# XMICRO-MEMORY.net
KiCad netlist of a schematic drawn in EAGLE
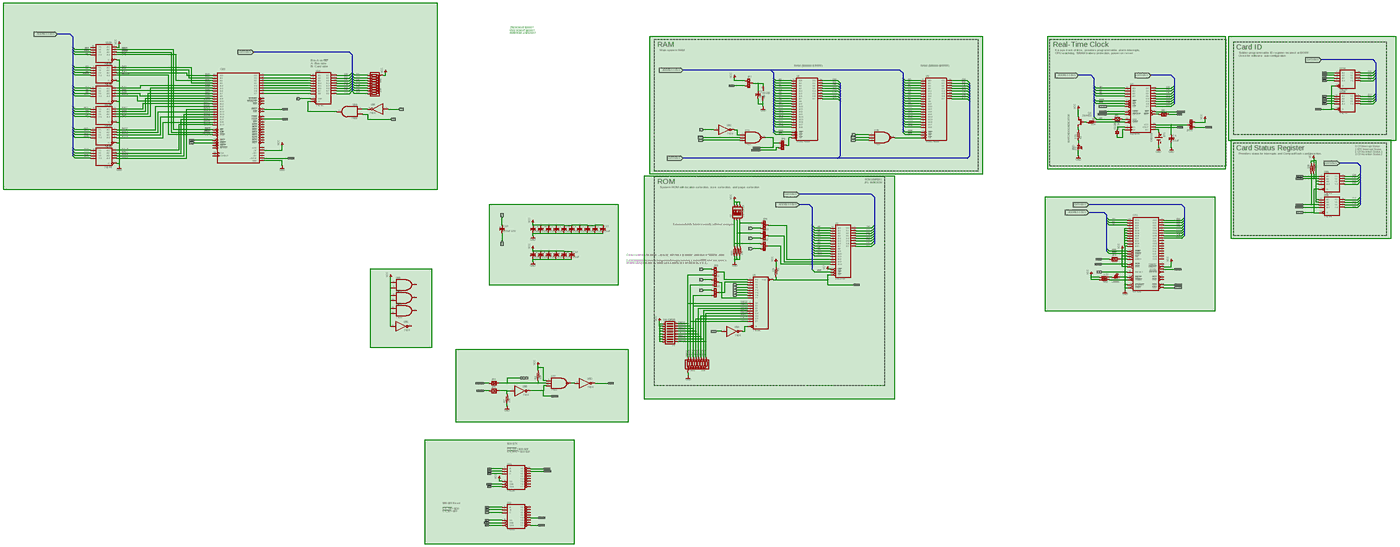
[diagram p0: schematic, sheet 1, overview]
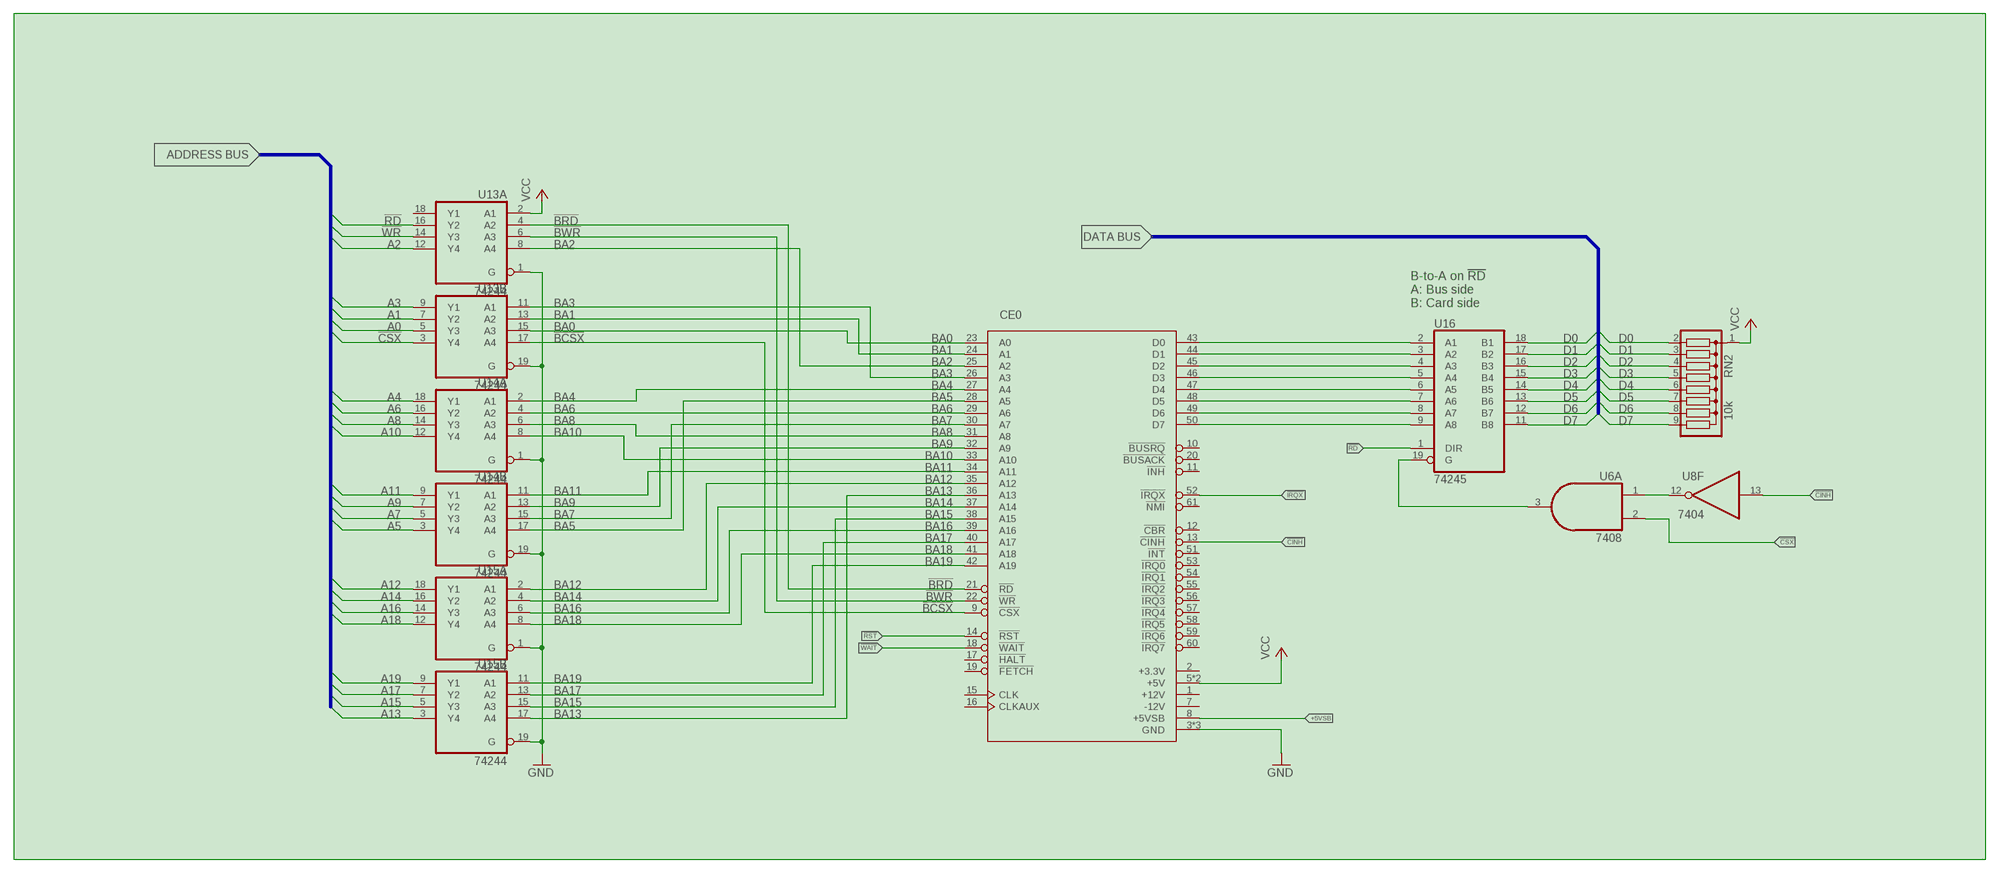
[diagram p1: schematic, sheet 1, part 1 of 6]
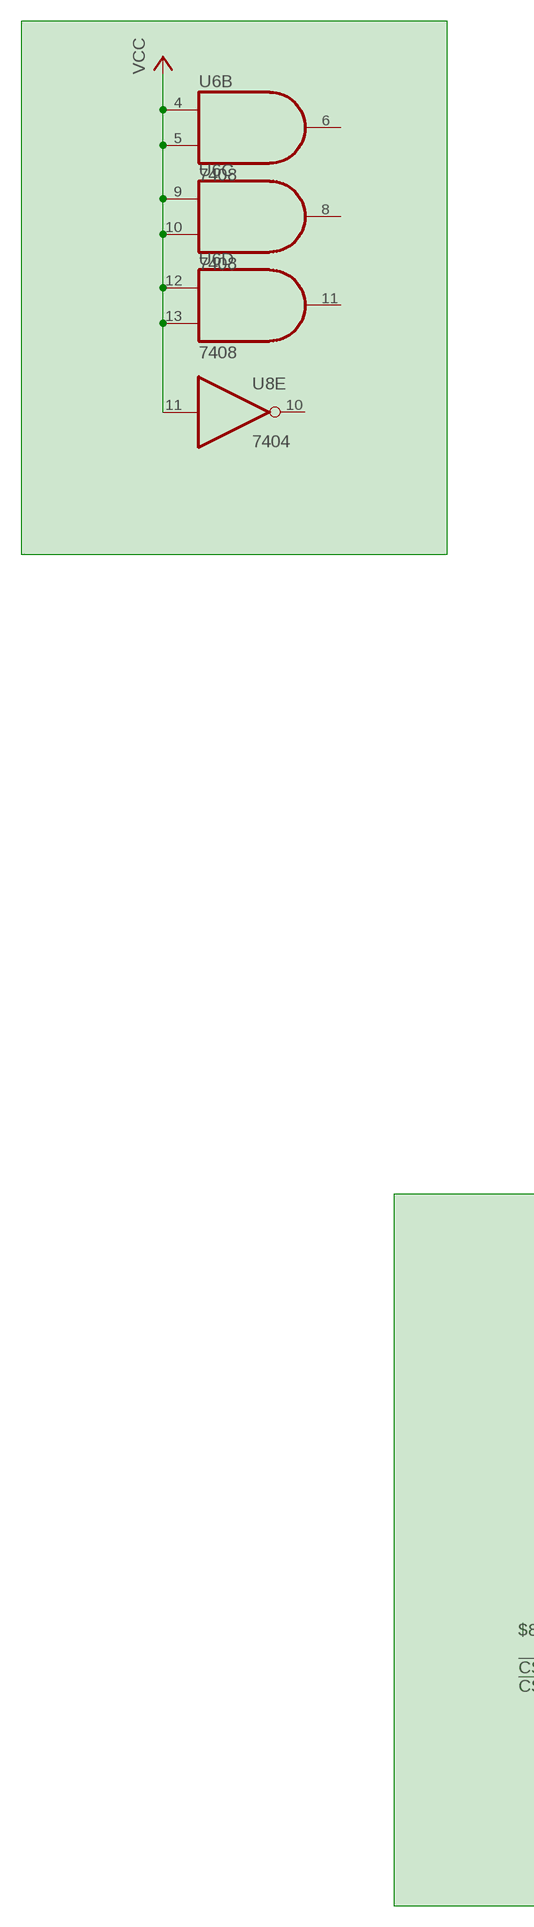
[diagram p2: schematic, sheet 1, part 2 of 6]
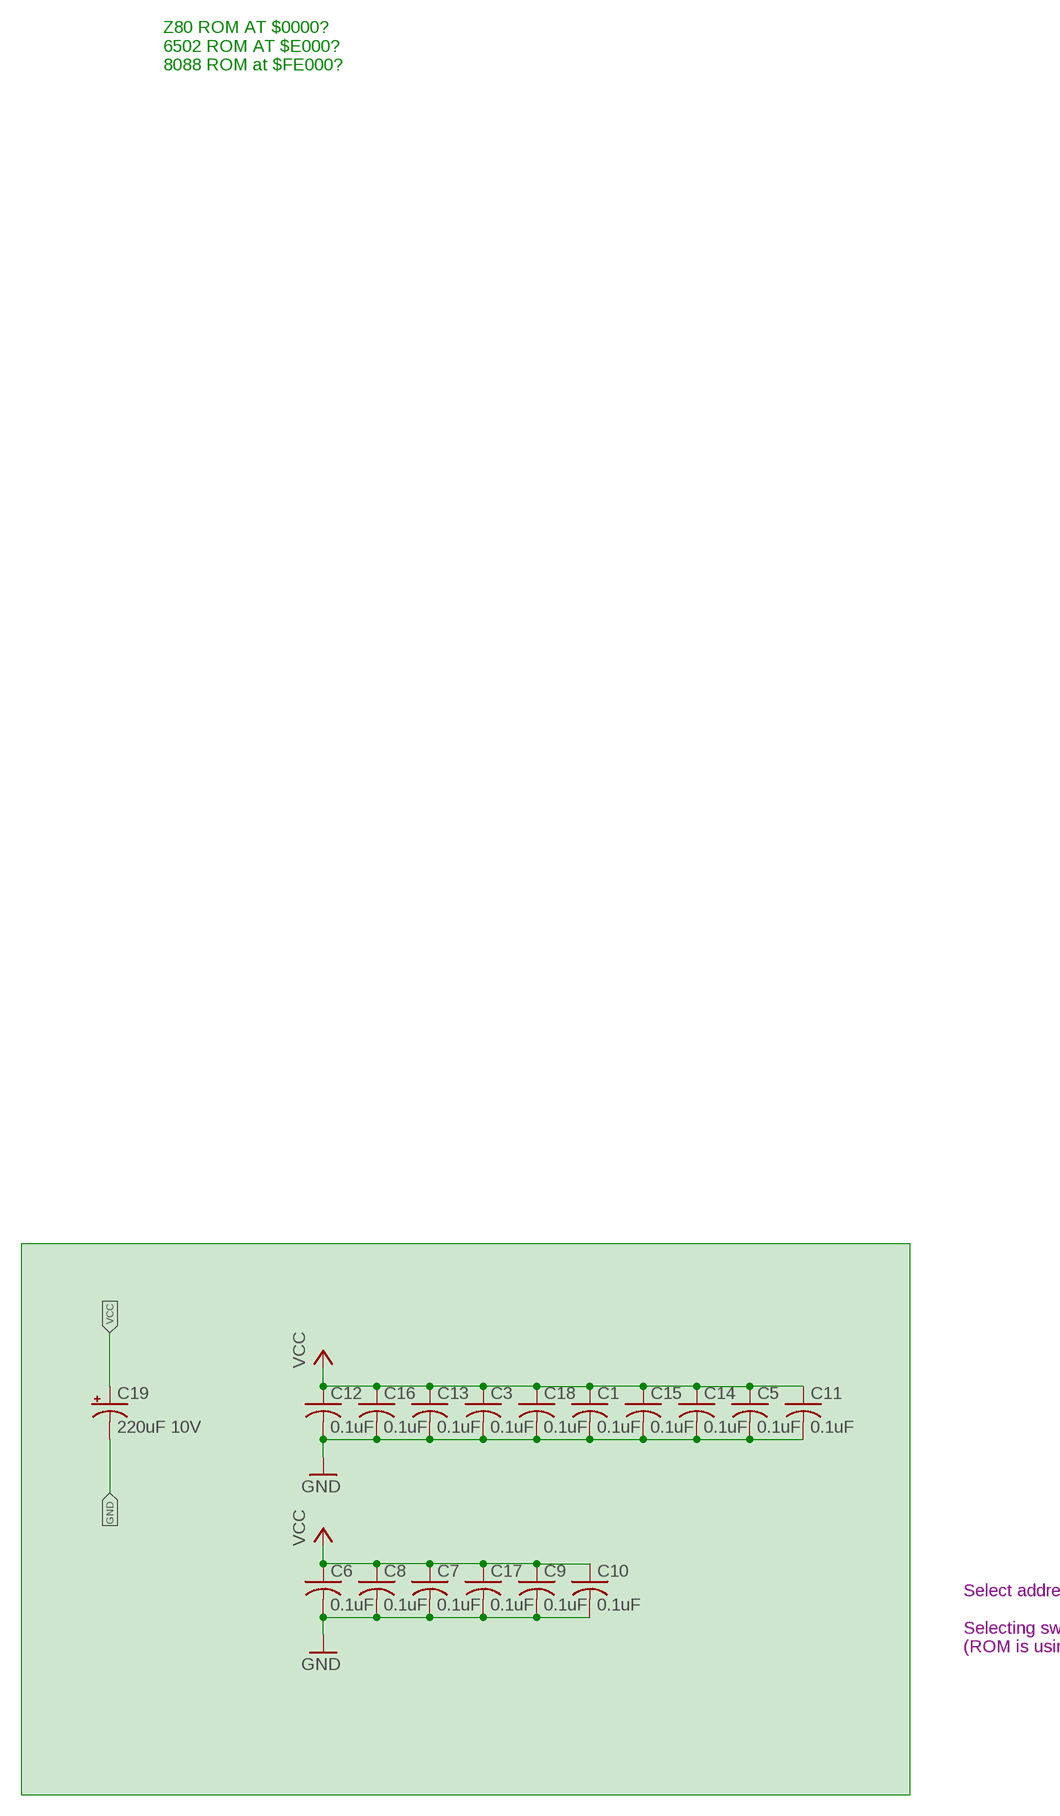
[diagram p3: schematic, sheet 1, part 3 of 6]
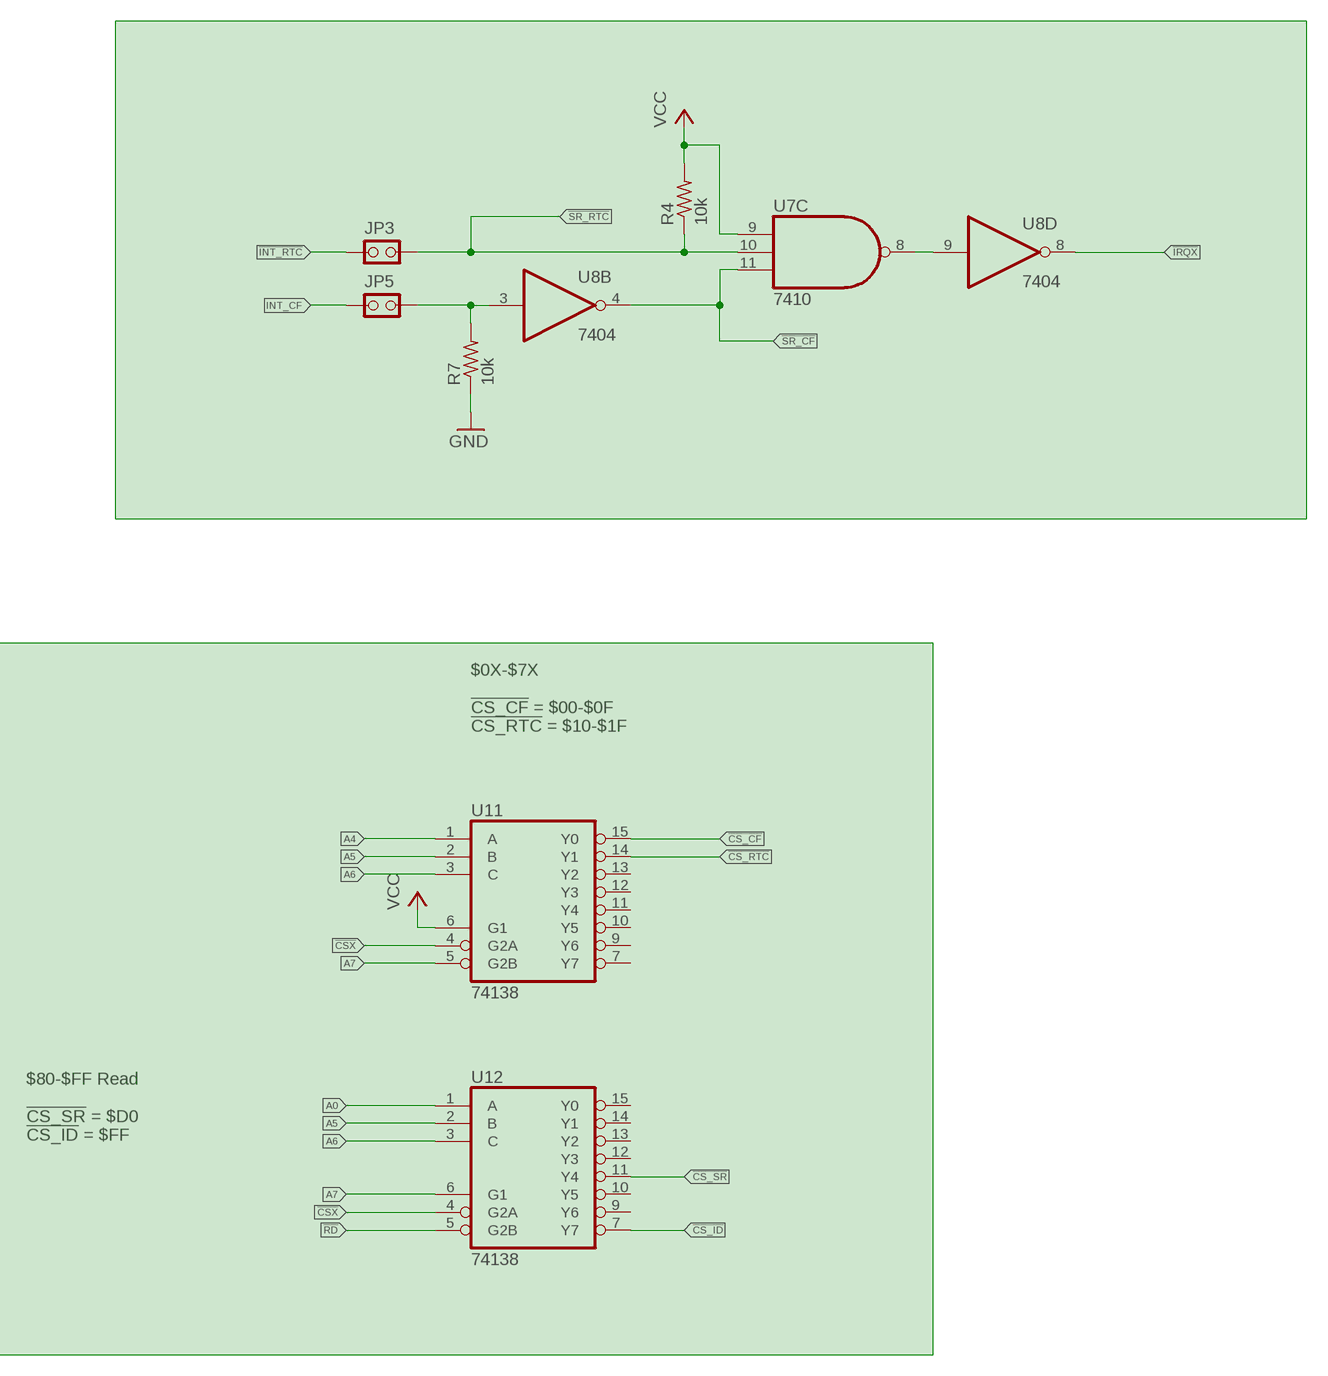
[diagram p4: schematic, sheet 1, part 4 of 6]
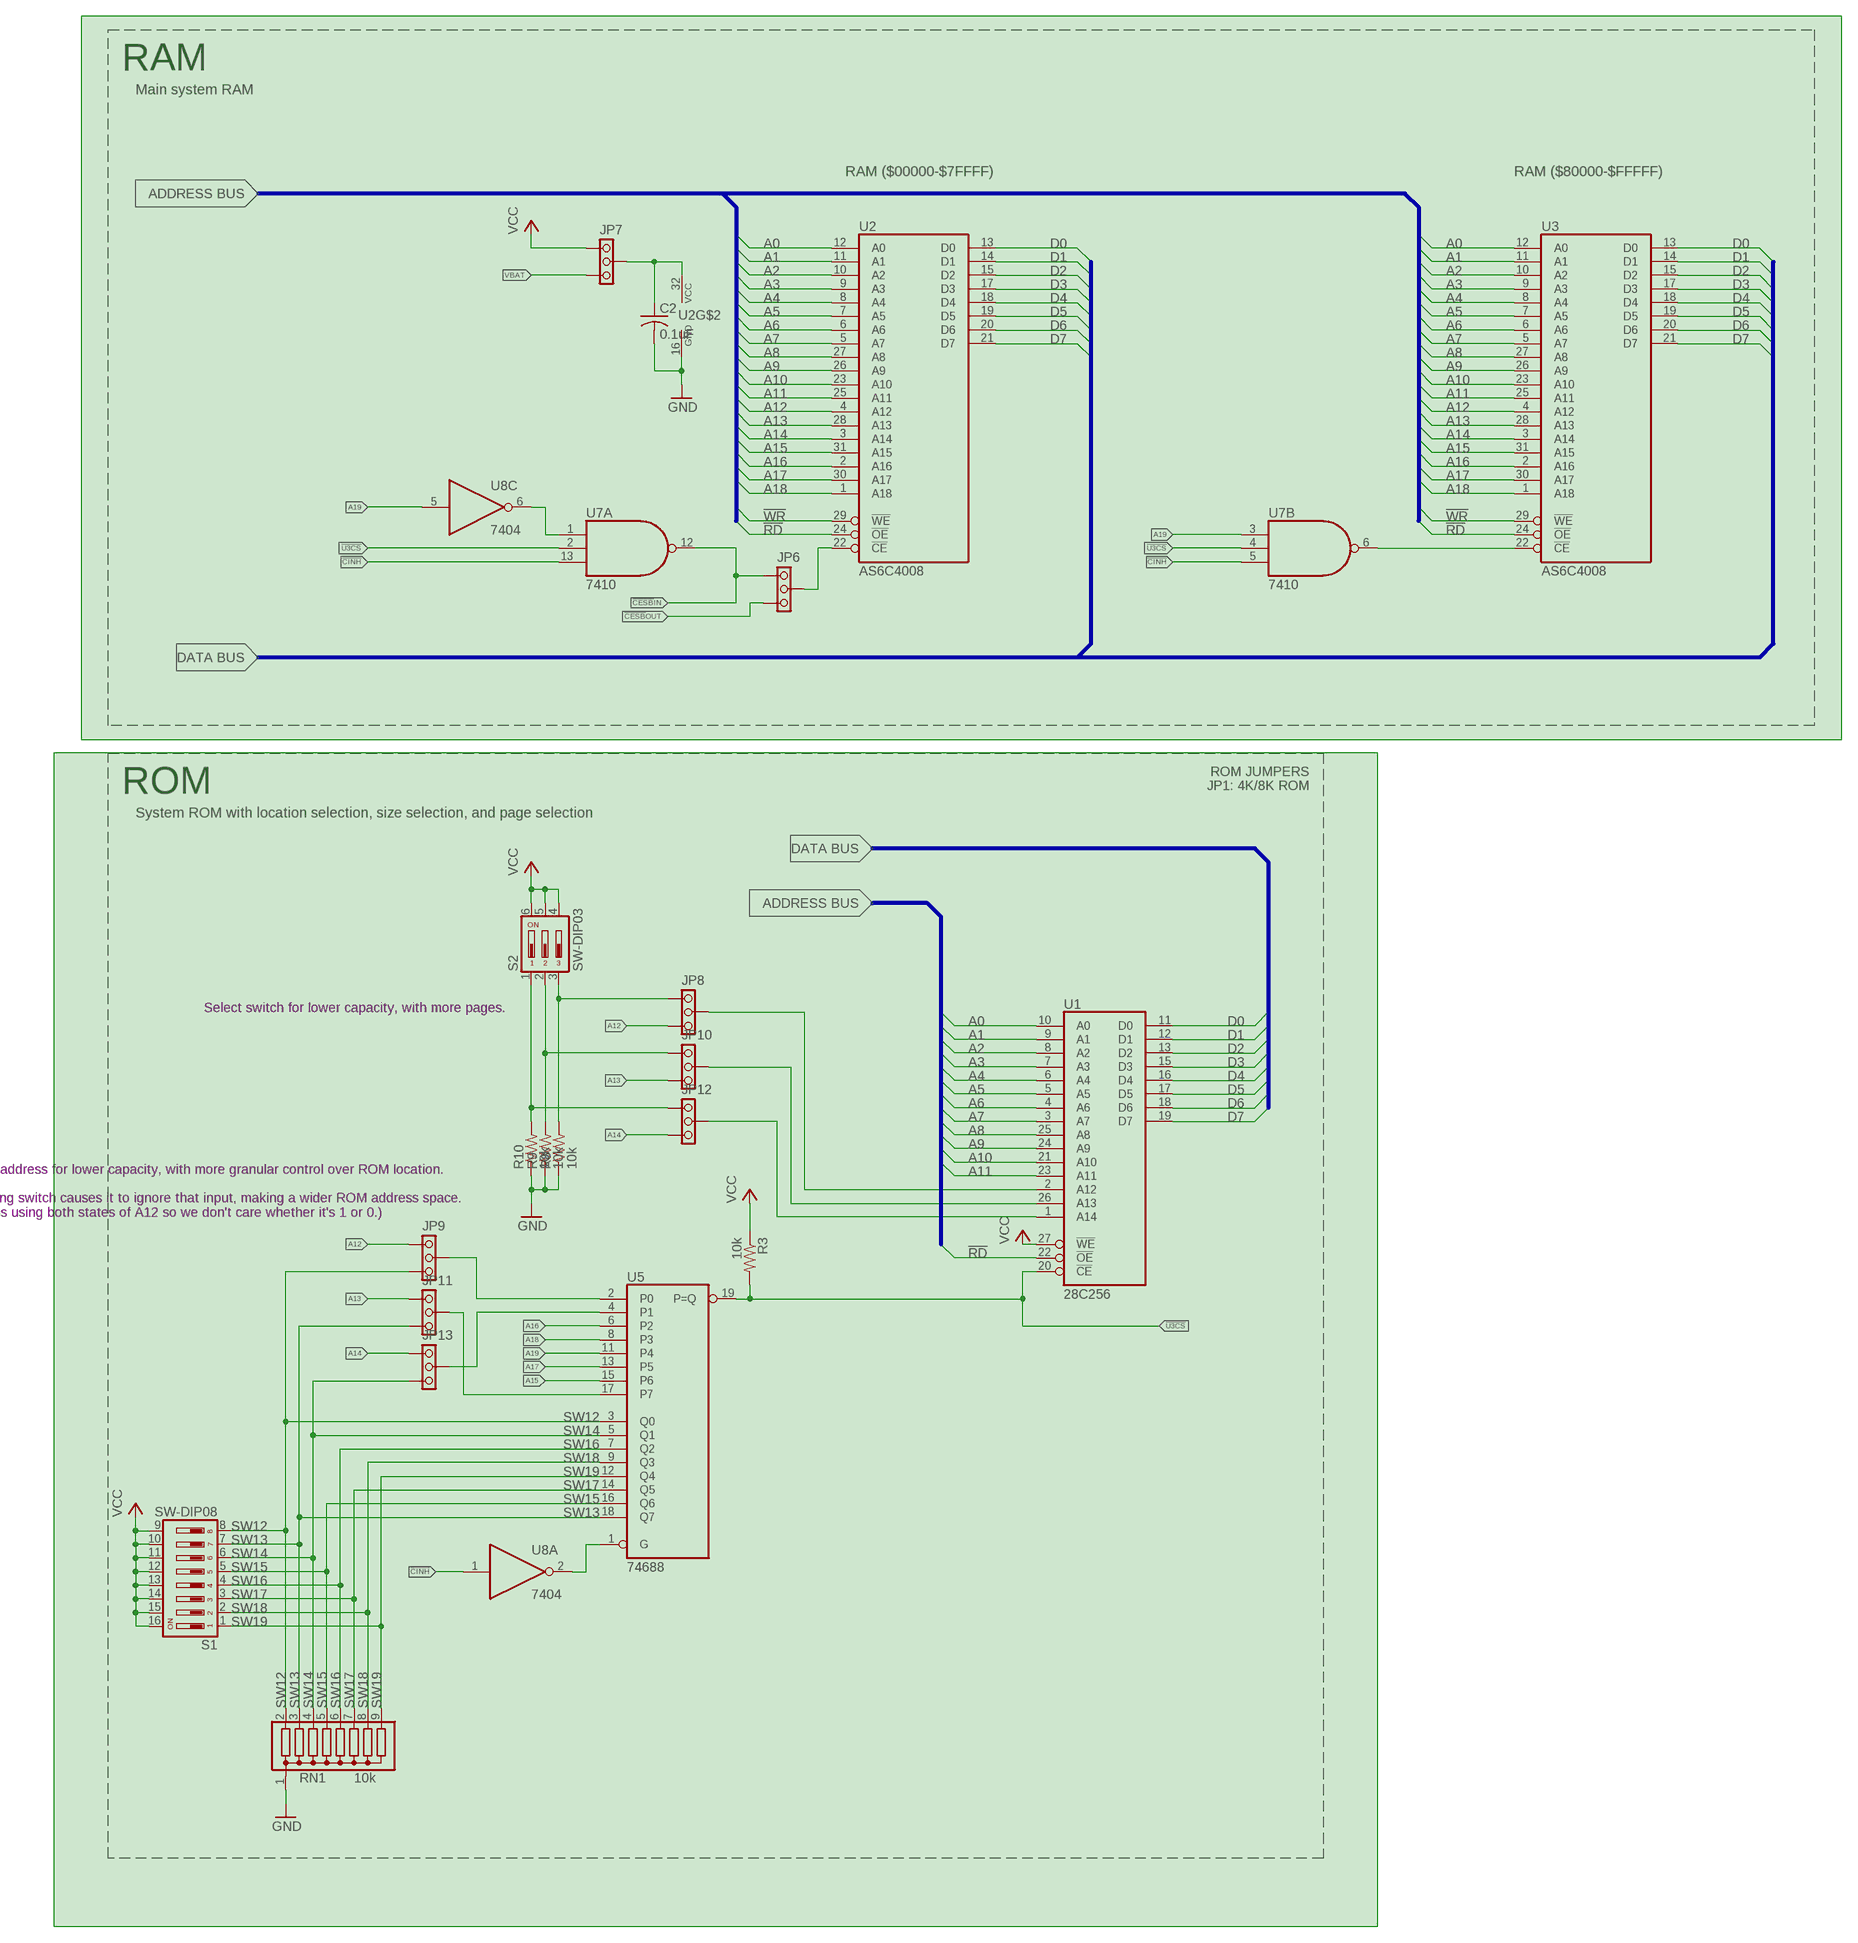
[diagram p5: schematic, sheet 1, part 5 of 6]
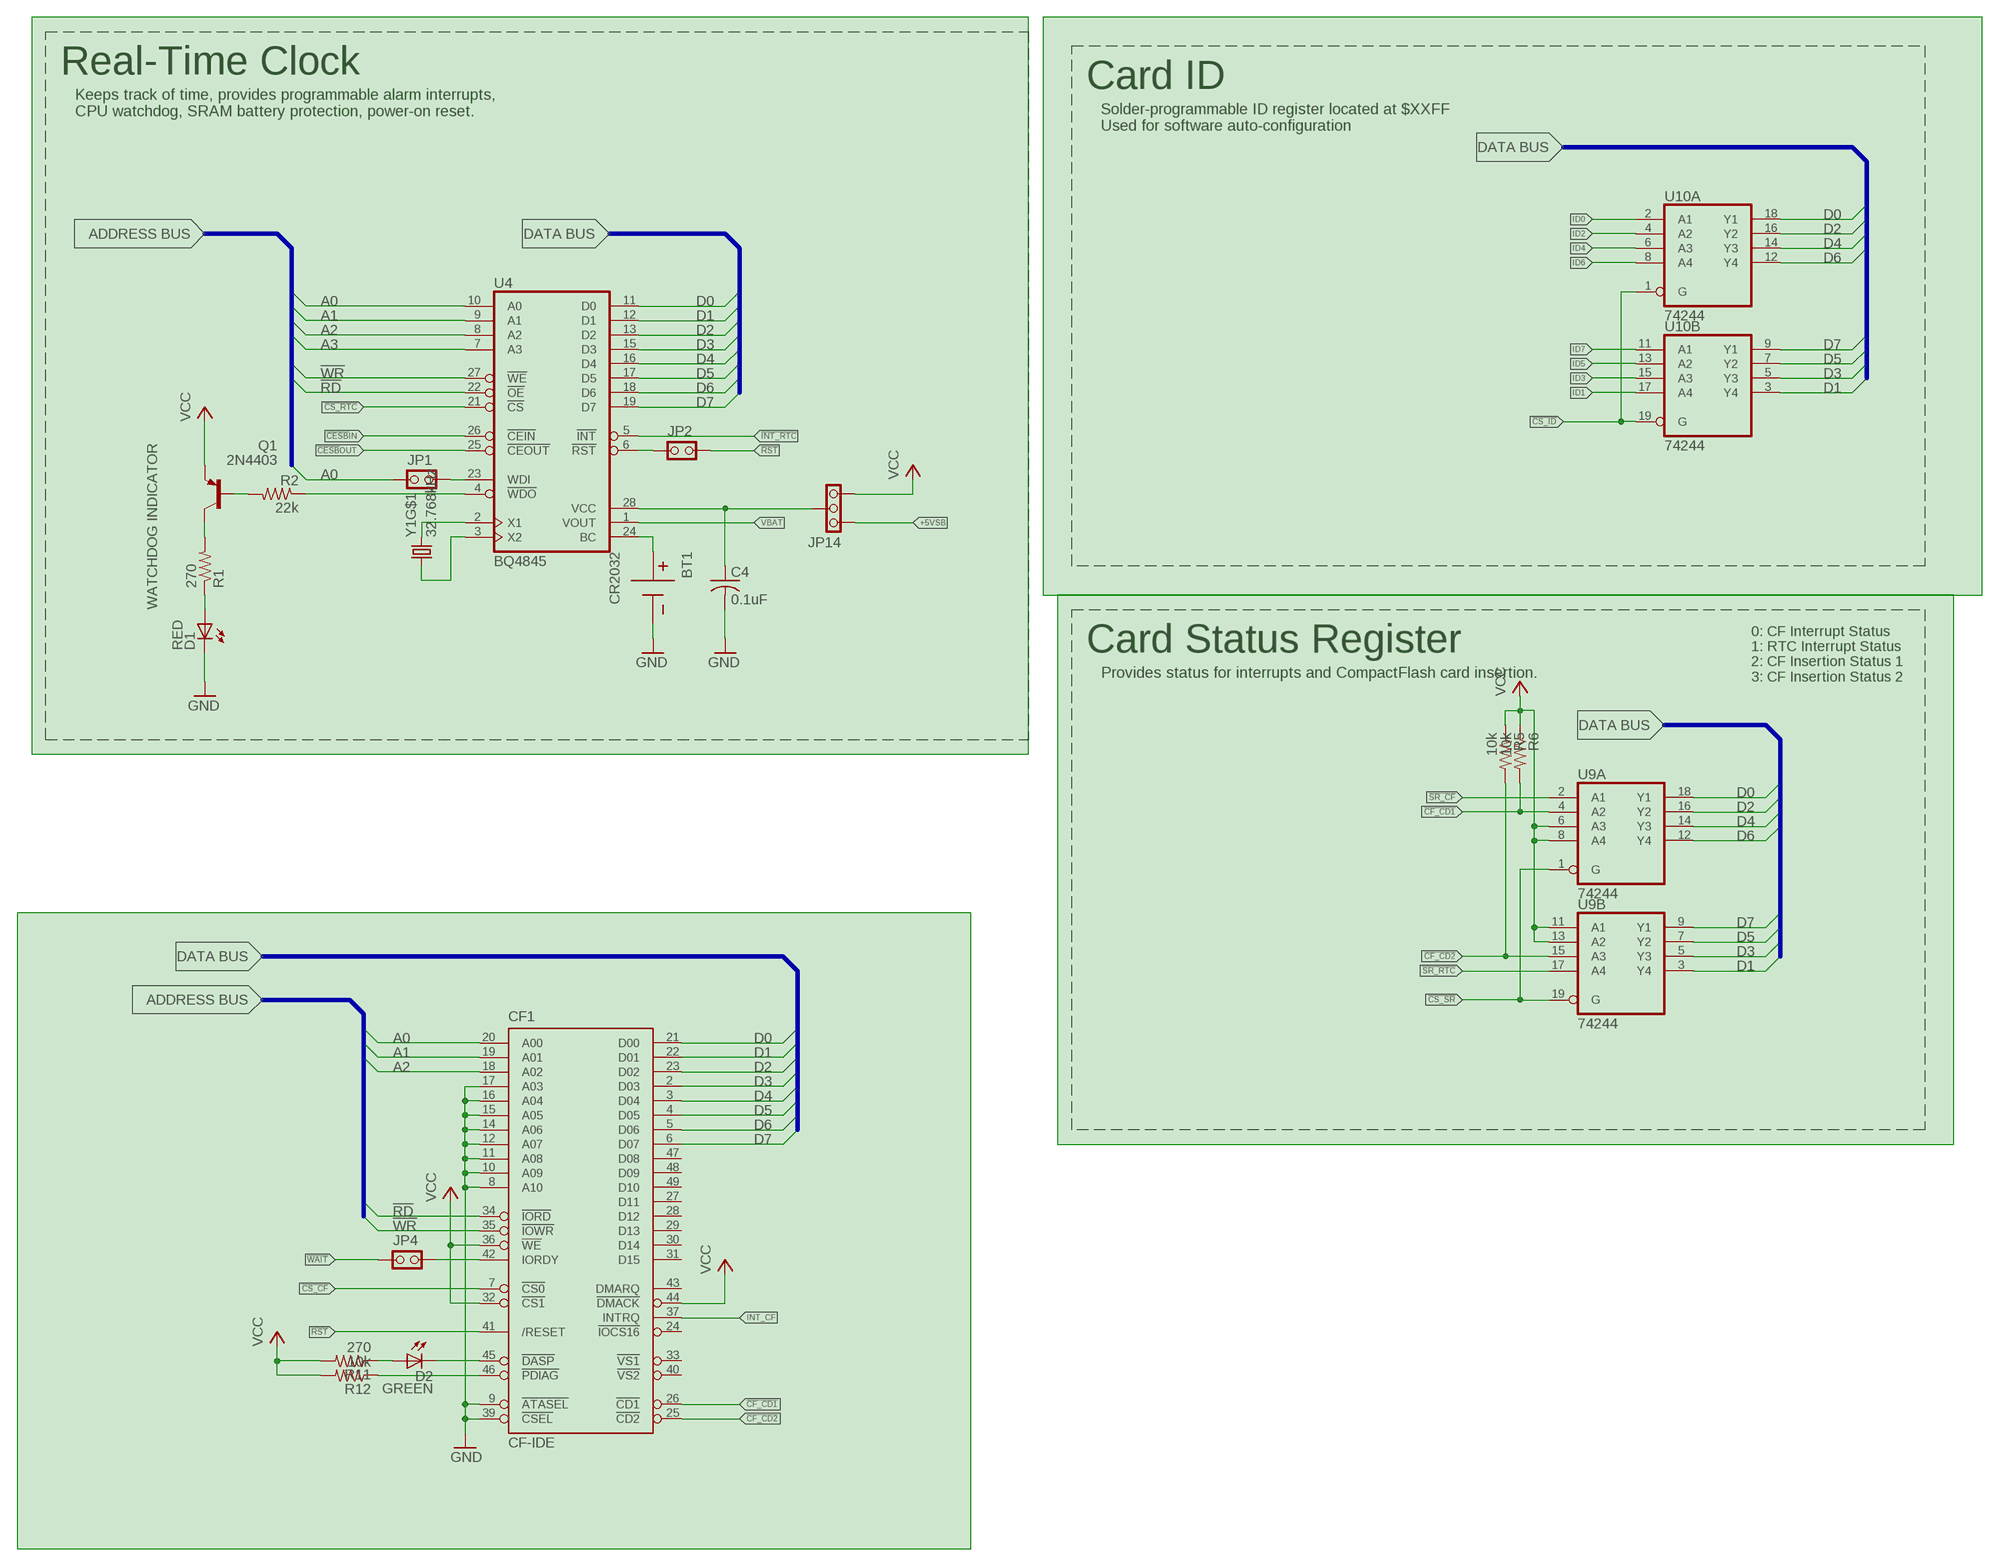
[diagram p6: schematic, sheet 1, part 6 of 6]

(export (version "E")
  (design (tool "Eeschema 10.0.6"))
  (components
    (comp (ref "BT1")
      (value "CR2032")
      (footprint "eagle-import:SMTU2032")
      (libsource (lib "eagle-import") (part "CR2032SMT"))
    )
    (comp (ref "C1")
      (value "0.1uF")
      (footprint "eagle-import:C025-024X044")
      (libsource (lib "eagle-import") (part "C-US025-024X044"))
    )
    (comp (ref "C2")
      (value "0.1uF")
      (footprint "eagle-import:C025-024X044")
      (libsource (lib "eagle-import") (part "C-US025-024X044"))
    )
    (comp (ref "C3")
      (value "0.1uF")
      (footprint "eagle-import:C025-024X044")
      (libsource (lib "eagle-import") (part "C-US025-024X044"))
    )
    (comp (ref "C4")
      (value "0.1uF")
      (footprint "eagle-import:C025-024X044")
      (libsource (lib "eagle-import") (part "C-US025-024X044"))
    )
    (comp (ref "C5")
      (value "0.1uF")
      (footprint "eagle-import:C025-024X044")
      (libsource (lib "eagle-import") (part "C-US025-024X044"))
    )
    (comp (ref "C6")
      (value "0.1uF")
      (footprint "eagle-import:C025-024X044")
      (libsource (lib "eagle-import") (part "C-US025-024X044"))
    )
    (comp (ref "C7")
      (value "0.1uF")
      (footprint "eagle-import:C025-024X044")
      (libsource (lib "eagle-import") (part "C-US025-024X044"))
    )
    (comp (ref "C8")
      (value "0.1uF")
      (footprint "eagle-import:C025-024X044")
      (libsource (lib "eagle-import") (part "C-US025-024X044"))
    )
    (comp (ref "C9")
      (value "0.1uF")
      (footprint "eagle-import:C025-024X044")
      (libsource (lib "eagle-import") (part "C-US025-024X044"))
    )
    (comp (ref "C10")
      (value "0.1uF")
      (footprint "eagle-import:C025-024X044")
      (libsource (lib "eagle-import") (part "C-US025-024X044"))
    )
    (comp (ref "C11")
      (value "0.1uF")
      (footprint "eagle-import:C025-024X044")
      (libsource (lib "eagle-import") (part "C-US025-024X044"))
    )
    (comp (ref "C12")
      (value "0.1uF")
      (footprint "eagle-import:C025-024X044")
      (libsource (lib "eagle-import") (part "C-US025-024X044"))
    )
    (comp (ref "C13")
      (value "0.1uF")
      (footprint "eagle-import:C025-024X044")
      (libsource (lib "eagle-import") (part "C-US025-024X044"))
    )
    (comp (ref "C14")
      (value "0.1uF")
      (footprint "eagle-import:C025-024X044")
      (libsource (lib "eagle-import") (part "C-US025-024X044"))
    )
    (comp (ref "C15")
      (value "0.1uF")
      (footprint "eagle-import:C025-024X044")
      (libsource (lib "eagle-import") (part "C-US025-024X044"))
    )
    (comp (ref "C16")
      (value "0.1uF")
      (footprint "eagle-import:C025-024X044")
      (libsource (lib "eagle-import") (part "C-US025-024X044"))
    )
    (comp (ref "C17")
      (value "0.1uF")
      (footprint "eagle-import:C025-024X044")
      (libsource (lib "eagle-import") (part "C-US025-024X044"))
    )
    (comp (ref "C18")
      (value "0.1uF")
      (footprint "eagle-import:C025-024X044")
      (libsource (lib "eagle-import") (part "C-US025-024X044"))
    )
    (comp (ref "C19")
      (value "220uF 10V")
      (footprint "eagle-import:C-10-5")
      (libsource (lib "eagle-import") (part "CPOL-US-10-5"))
    )
    (comp (ref "CE0")
      (value "XMICRO-BUS-EDGE62M")
      (footprint "eagle-import:EDGE62M")
      (libsource (lib "eagle-import") (part "XMICRO-BUS-EDGE62M"))
    )
    (comp (ref "CF1")
      (value "CF-IDE")
      (footprint "eagle-import:CF-KYOCERA")
      (libsource (lib "eagle-import") (part "CF-IDE"))
    )
    (comp (ref "D1")
      (value "RED")
      (footprint "eagle-import:LED5MM")
      (libsource (lib "eagle-import") (part "LED5MM"))
    )
    (comp (ref "D2")
      (value "GREEN")
      (footprint "eagle-import:LED-3-R")
      (libsource (lib "eagle-import") (part "LED-3-R"))
    )
    (comp (ref "JP1")
      (value "PINHD-1X2THRU")
      (footprint "eagle-import:1X02")
      (libsource (lib "eagle-import") (part "PINHD-1X2THRU"))
    )
    (comp (ref "JP2")
      (value "PINHD-1X2THRU")
      (footprint "eagle-import:1X02")
      (libsource (lib "eagle-import") (part "PINHD-1X2THRU"))
    )
    (comp (ref "JP3")
      (value "PINHD-1X2THRU")
      (footprint "eagle-import:1X02")
      (libsource (lib "eagle-import") (part "PINHD-1X2THRU"))
    )
    (comp (ref "JP4")
      (value "PINHD-1X2THRU")
      (footprint "eagle-import:1X02")
      (libsource (lib "eagle-import") (part "PINHD-1X2THRU"))
    )
    (comp (ref "JP5")
      (value "PINHD-1X2THRU")
      (footprint "eagle-import:1X02")
      (libsource (lib "eagle-import") (part "PINHD-1X2THRU"))
    )
    (comp (ref "JP6")
      (value "PINHD1X3THRU")
      (footprint "eagle-import:1X03")
      (libsource (lib "eagle-import") (part "PINHD1X3THRU"))
    )
    (comp (ref "JP7")
      (value "PINHD1X3THRU")
      (footprint "eagle-import:1X03")
      (libsource (lib "eagle-import") (part "PINHD1X3THRU"))
    )
    (comp (ref "JP8")
      (value "PINHD1X3THRU")
      (footprint "eagle-import:1X03")
      (libsource (lib "eagle-import") (part "PINHD1X3THRU"))
    )
    (comp (ref "JP9")
      (value "PINHD1X3THRU")
      (footprint "eagle-import:1X03")
      (libsource (lib "eagle-import") (part "PINHD1X3THRU"))
    )
    (comp (ref "JP10")
      (value "PINHD1X3THRU")
      (footprint "eagle-import:1X03")
      (libsource (lib "eagle-import") (part "PINHD1X3THRU"))
    )
    (comp (ref "JP11")
      (value "PINHD1X3THRU")
      (footprint "eagle-import:1X03")
      (libsource (lib "eagle-import") (part "PINHD1X3THRU"))
    )
    (comp (ref "JP12")
      (value "PINHD1X3THRU")
      (footprint "eagle-import:1X03")
      (libsource (lib "eagle-import") (part "PINHD1X3THRU"))
    )
    (comp (ref "JP13")
      (value "PINHD1X3THRU")
      (footprint "eagle-import:1X03")
      (libsource (lib "eagle-import") (part "PINHD1X3THRU"))
    )
    (comp (ref "JP14")
      (value "PINHD1X3THRU")
      (footprint "eagle-import:1X03")
      (libsource (lib "eagle-import") (part "PINHD1X3THRU"))
    )
    (comp (ref "Q1")
      (value "2N4403")
      (footprint "eagle-import:TO92")
      (libsource (lib "eagle-import") (part "TRANSISTOR-PNP-2N4403"))
    )
    (comp (ref "R1")
      (value "270")
      (footprint "eagle-import:0207_10")
      (libsource (lib "eagle-import") (part "R-US_0207/10"))
    )
    (comp (ref "R2")
      (value "22k")
      (footprint "eagle-import:0207_10")
      (libsource (lib "eagle-import") (part "R-US_0207/10"))
    )
    (comp (ref "R3")
      (value "10k")
      (footprint "eagle-import:0207_10")
      (libsource (lib "eagle-import") (part "R-US_0207/10"))
    )
    (comp (ref "R4")
      (value "10k")
      (footprint "eagle-import:0207_10")
      (libsource (lib "eagle-import") (part "R-US_0207/10"))
    )
    (comp (ref "R5")
      (value "10k")
      (footprint "eagle-import:0207_10")
      (libsource (lib "eagle-import") (part "R-US_0207/10"))
    )
    (comp (ref "R6")
      (value "10k")
      (footprint "eagle-import:0207_10")
      (libsource (lib "eagle-import") (part "R-US_0207/10"))
    )
    (comp (ref "R7")
      (value "10k")
      (footprint "eagle-import:0207_10")
      (libsource (lib "eagle-import") (part "R-US_0207/10"))
    )
    (comp (ref "R8")
      (value "10k")
      (footprint "eagle-import:0207_10")
      (libsource (lib "eagle-import") (part "R-US_0207/10"))
    )
    (comp (ref "R9")
      (value "10k")
      (footprint "eagle-import:0207_10")
      (libsource (lib "eagle-import") (part "R-US_0207/10"))
    )
    (comp (ref "R10")
      (value "10k")
      (footprint "eagle-import:0207_10")
      (libsource (lib "eagle-import") (part "R-US_0207/10"))
    )
    (comp (ref "R11")
      (value "270")
      (footprint "eagle-import:0207_10")
      (libsource (lib "eagle-import") (part "R-US_0207/10"))
    )
    (comp (ref "R12")
      (value "10k")
      (footprint "eagle-import:0207_10")
      (libsource (lib "eagle-import") (part "R-US_0207/10"))
    )
    (comp (ref "RN1")
      (value "10k")
      (footprint "eagle-import:SIL9")
      (libsource (lib "eagle-import") (part "G08R"))
    )
    (comp (ref "RN2")
      (value "10k")
      (footprint "eagle-import:SIL9")
      (fields (field (name "OC_FARNELL") "unknown") (field (name "OC_NEWARK") "unknown"))
      (libsource (lib "eagle-import") (part "G08R"))
    )
    (comp (ref "S1")
      (value "SW-DIP08")
      (footprint "eagle-import:SW-DIP8")
      (libsource (lib "eagle-import") (part "SW-DIP08"))
    )
    (comp (ref "S2")
      (value "SW-DIP03")
      (footprint "eagle-import:SW-DIP3")
      (libsource (lib "eagle-import") (part "SW-DIP03"))
    )
    (comp (ref "U1")
      (value "28C256")
      (footprint "eagle-import:228-1277-00")
      (libsource (lib "eagle-import") (part "28256-ZIF28"))
    )
    (comp (ref "U2")
      (value "AS6C4008")
      (footprint "eagle-import:DIL32-6")
      (libsource (lib "eagle-import") (part "4008"))
    )
    (comp (ref "U3")
      (value "AS6C4008")
      (footprint "eagle-import:DIL32-6")
      (libsource (lib "eagle-import") (part "4008"))
    )
    (comp (ref "U4")
      (value "BQ4845")
      (footprint "eagle-import:DIL28")
      (libsource (lib "eagle-import") (part "BQ4845"))
    )
    (comp (ref "U5")
      (value "74688")
      (footprint "eagle-import:DIL20")
      (libsource (lib "eagle-import") (part "74688NLS"))
    )
    (comp (ref "U6")
      (value "7408")
      (footprint "eagle-import:DIL14")
      (libsource (lib "eagle-import") (part "7408NLS"))
    )
    (comp (ref "U7")
      (value "7410")
      (footprint "eagle-import:DIL14")
      (libsource (lib "eagle-import") (part "7410NLS"))
    )
    (comp (ref "U8")
      (value "7404")
      (footprint "eagle-import:DIL14")
      (libsource (lib "eagle-import") (part "7404NLS"))
    )
    (comp (ref "U9")
      (value "74244")
      (footprint "eagle-import:DIL20")
      (libsource (lib "eagle-import") (part "74244NLS"))
    )
    (comp (ref "U10")
      (value "74244")
      (footprint "eagle-import:DIL20")
      (libsource (lib "eagle-import") (part "74244NLS"))
    )
    (comp (ref "U11")
      (value "74138")
      (footprint "eagle-import:DIL16")
      (libsource (lib "eagle-import") (part "74138NLS"))
    )
    (comp (ref "U12")
      (value "74138")
      (footprint "eagle-import:DIL16")
      (libsource (lib "eagle-import") (part "74138NLS"))
    )
    (comp (ref "U13")
      (value "74244")
      (footprint "eagle-import:DIL20")
      (libsource (lib "eagle-import") (part "74244NLS"))
    )
    (comp (ref "U14")
      (value "74244")
      (footprint "eagle-import:DIL20")
      (libsource (lib "eagle-import") (part "74244NLS"))
    )
    (comp (ref "U15")
      (value "74244")
      (footprint "eagle-import:DIL20")
      (libsource (lib "eagle-import") (part "74244NLS"))
    )
    (comp (ref "U16")
      (value "74245")
      (footprint "eagle-import:DIL20")
      (libsource (lib "eagle-import") (part "74245NLS"))
    )
    (comp (ref "Y1")
      (value "32.768kHz")
      (footprint "eagle-import:CRYSTAL-3X8H")
      (libsource (lib "eagle-import") (part "CRYSTAL"))
    )
  )
  (nets
    (net (code "1") (name "+5VSB") (class "Default")
      (node (ref "CE0") (pin "8") (pinfunction "+5VSB_8") (pintype "bidirectional"))
      (node (ref "JP14") (pin "1") (pinfunction "1_1") (pintype "passive"))
    )
    (net (code "4") (name "A0") (class "Default")
      (node (ref "CF1") (pin "20") (pinfunction "A00_20") (pintype "input"))
      (node (ref "JP1") (pin "1") (pinfunction "1_1") (pintype "passive"))
      (node (ref "U1") (pin "10") (pinfunction "A0_10") (pintype "input"))
      (node (ref "U12") (pin "1") (pinfunction "A_1") (pintype "input"))
      (node (ref "U13") (pin "5") (pinfunction "Y3_5") (pintype "tri_state"))
      (node (ref "U2") (pin "12") (pinfunction "A0_12") (pintype "input"))
      (node (ref "U3") (pin "12") (pinfunction "A0_12") (pintype "input"))
      (node (ref "U4") (pin "10") (pinfunction "A0_10") (pintype "input"))
    )
    (net (code "5") (name "A1") (class "Default")
      (node (ref "CF1") (pin "19") (pinfunction "A01_19") (pintype "input"))
      (node (ref "U1") (pin "9") (pinfunction "A1_9") (pintype "input"))
      (node (ref "U13") (pin "7") (pinfunction "Y2_7") (pintype "tri_state"))
      (node (ref "U2") (pin "11") (pinfunction "A1_11") (pintype "input"))
      (node (ref "U3") (pin "11") (pinfunction "A1_11") (pintype "input"))
      (node (ref "U4") (pin "9") (pinfunction "A1_9") (pintype "input"))
    )
    (net (code "6") (name "A2") (class "Default")
      (node (ref "CF1") (pin "18") (pinfunction "A02_18") (pintype "input"))
      (node (ref "U1") (pin "8") (pinfunction "A2_8") (pintype "input"))
      (node (ref "U13") (pin "12") (pinfunction "Y4_12") (pintype "tri_state"))
      (node (ref "U2") (pin "10") (pinfunction "A2_10") (pintype "input"))
      (node (ref "U3") (pin "10") (pinfunction "A2_10") (pintype "input"))
      (node (ref "U4") (pin "8") (pinfunction "A2_8") (pintype "input"))
    )
    (net (code "7") (name "A3") (class "Default")
      (node (ref "U1") (pin "7") (pinfunction "A3_7") (pintype "input"))
      (node (ref "U13") (pin "9") (pinfunction "Y1_9") (pintype "tri_state"))
      (node (ref "U2") (pin "9") (pinfunction "A3_9") (pintype "input"))
      (node (ref "U3") (pin "9") (pinfunction "A3_9") (pintype "input"))
      (node (ref "U4") (pin "7") (pinfunction "A3_7") (pintype "input"))
    )
    (net (code "8") (name "A4") (class "Default")
      (node (ref "U1") (pin "6") (pinfunction "A4_6") (pintype "input"))
      (node (ref "U11") (pin "1") (pinfunction "A_1") (pintype "input"))
      (node (ref "U14") (pin "18") (pinfunction "Y1_18") (pintype "tri_state"))
      (node (ref "U2") (pin "8") (pinfunction "A4_8") (pintype "input"))
      (node (ref "U3") (pin "8") (pinfunction "A4_8") (pintype "input"))
    )
    (net (code "9") (name "A5") (class "Default")
      (node (ref "U1") (pin "5") (pinfunction "A5_5") (pintype "input"))
      (node (ref "U11") (pin "2") (pinfunction "B_2") (pintype "input"))
      (node (ref "U12") (pin "2") (pinfunction "B_2") (pintype "input"))
      (node (ref "U14") (pin "3") (pinfunction "Y4_3") (pintype "tri_state"))
      (node (ref "U2") (pin "7") (pinfunction "A5_7") (pintype "input"))
      (node (ref "U3") (pin "7") (pinfunction "A5_7") (pintype "input"))
    )
    (net (code "10") (name "A6") (class "Default")
      (node (ref "U1") (pin "4") (pinfunction "A6_4") (pintype "input"))
      (node (ref "U11") (pin "3") (pinfunction "C_3") (pintype "input"))
      (node (ref "U12") (pin "3") (pinfunction "C_3") (pintype "input"))
      (node (ref "U14") (pin "16") (pinfunction "Y2_16") (pintype "tri_state"))
      (node (ref "U2") (pin "6") (pinfunction "A6_6") (pintype "input"))
      (node (ref "U3") (pin "6") (pinfunction "A6_6") (pintype "input"))
    )
    (net (code "11") (name "A7") (class "Default")
      (node (ref "U1") (pin "3") (pinfunction "A7_3") (pintype "input"))
      (node (ref "U11") (pin "5") (pinfunction "G2B_5") (pintype "input"))
      (node (ref "U12") (pin "6") (pinfunction "G1_6") (pintype "input"))
      (node (ref "U14") (pin "5") (pinfunction "Y3_5") (pintype "tri_state"))
      (node (ref "U2") (pin "5") (pinfunction "A7_5") (pintype "input"))
      (node (ref "U3") (pin "5") (pinfunction "A7_5") (pintype "input"))
    )
    (net (code "12") (name "A8") (class "Default")
      (node (ref "U1") (pin "25") (pinfunction "A8_25") (pintype "input"))
      (node (ref "U14") (pin "14") (pinfunction "Y3_14") (pintype "tri_state"))
      (node (ref "U2") (pin "27") (pinfunction "A8_27") (pintype "input"))
      (node (ref "U3") (pin "27") (pinfunction "A8_27") (pintype "input"))
    )
    (net (code "13") (name "A9") (class "Default")
      (node (ref "U1") (pin "24") (pinfunction "A9_24") (pintype "input"))
      (node (ref "U14") (pin "7") (pinfunction "Y2_7") (pintype "tri_state"))
      (node (ref "U2") (pin "26") (pinfunction "A9_26") (pintype "input"))
      (node (ref "U3") (pin "26") (pinfunction "A9_26") (pintype "input"))
    )
    (net (code "14") (name "A10") (class "Default")
      (node (ref "U1") (pin "21") (pinfunction "A10_21") (pintype "input"))
      (node (ref "U14") (pin "12") (pinfunction "Y4_12") (pintype "tri_state"))
      (node (ref "U2") (pin "23") (pinfunction "A10_23") (pintype "input"))
      (node (ref "U3") (pin "23") (pinfunction "A10_23") (pintype "input"))
    )
    (net (code "15") (name "A11") (class "Default")
      (node (ref "U1") (pin "23") (pinfunction "A11_23") (pintype "input"))
      (node (ref "U14") (pin "9") (pinfunction "Y1_9") (pintype "tri_state"))
      (node (ref "U2") (pin "25") (pinfunction "A11_25") (pintype "input"))
      (node (ref "U3") (pin "25") (pinfunction "A11_25") (pintype "input"))
    )
    (net (code "16") (name "A12") (class "Default")
      (node (ref "JP8") (pin "3") (pinfunction "3_3") (pintype "passive"))
      (node (ref "JP9") (pin "1") (pinfunction "1_1") (pintype "passive"))
      (node (ref "U15") (pin "18") (pinfunction "Y1_18") (pintype "tri_state"))
      (node (ref "U2") (pin "4") (pinfunction "A12_4") (pintype "input"))
      (node (ref "U3") (pin "4") (pinfunction "A12_4") (pintype "input"))
    )
    (net (code "17") (name "A13") (class "Default")
      (node (ref "JP10") (pin "3") (pinfunction "3_3") (pintype "passive"))
      (node (ref "JP11") (pin "1") (pinfunction "1_1") (pintype "passive"))
      (node (ref "U15") (pin "3") (pinfunction "Y4_3") (pintype "tri_state"))
      (node (ref "U2") (pin "28") (pinfunction "A13_28") (pintype "input"))
      (node (ref "U3") (pin "28") (pinfunction "A13_28") (pintype "input"))
    )
    (net (code "18") (name "A14") (class "Default")
      (node (ref "JP12") (pin "3") (pinfunction "3_3") (pintype "passive"))
      (node (ref "JP13") (pin "1") (pinfunction "1_1") (pintype "passive"))
      (node (ref "U15") (pin "16") (pinfunction "Y2_16") (pintype "tri_state"))
      (node (ref "U2") (pin "3") (pinfunction "A14_3") (pintype "input"))
      (node (ref "U3") (pin "3") (pinfunction "A14_3") (pintype "input"))
    )
    (net (code "19") (name "A15") (class "Default")
      (node (ref "U15") (pin "5") (pinfunction "Y3_5") (pintype "tri_state"))
      (node (ref "U2") (pin "31") (pinfunction "A15_31") (pintype "input"))
      (node (ref "U3") (pin "31") (pinfunction "A15_31") (pintype "input"))
      (node (ref "U5") (pin "15") (pinfunction "P6_15") (pintype "input"))
    )
    (net (code "20") (name "A16") (class "Default")
      (node (ref "U15") (pin "14") (pinfunction "Y3_14") (pintype "tri_state"))
      (node (ref "U2") (pin "2") (pinfunction "A16_2") (pintype "input"))
      (node (ref "U3") (pin "2") (pinfunction "A16_2") (pintype "input"))
      (node (ref "U5") (pin "6") (pinfunction "P2_6") (pintype "input"))
    )
    (net (code "21") (name "A17") (class "Default")
      (node (ref "U15") (pin "7") (pinfunction "Y2_7") (pintype "tri_state"))
      (node (ref "U2") (pin "30") (pinfunction "A17_30") (pintype "input"))
      (node (ref "U3") (pin "30") (pinfunction "A17_30") (pintype "input"))
      (node (ref "U5") (pin "13") (pinfunction "P5_13") (pintype "input"))
    )
    (net (code "22") (name "A18") (class "Default")
      (node (ref "U15") (pin "12") (pinfunction "Y4_12") (pintype "tri_state"))
      (node (ref "U2") (pin "1") (pinfunction "A18_1") (pintype "input"))
      (node (ref "U3") (pin "1") (pinfunction "A18_1") (pintype "input"))
      (node (ref "U5") (pin "8") (pinfunction "P3_8") (pintype "input"))
    )
    (net (code "23") (name "A19") (class "Default")
      (node (ref "U15") (pin "9") (pinfunction "Y1_9") (pintype "tri_state"))
      (node (ref "U5") (pin "11") (pinfunction "P4_11") (pintype "input"))
      (node (ref "U7") (pin "3") (pinfunction "I0_3") (pintype "input"))
      (node (ref "U8") (pin "5") (pinfunction "I_5") (pintype "input"))
    )
    (net (code "24") (name "BA0") (class "Default")
      (node (ref "CE0") (pin "23") (pinfunction "A0_23") (pintype "bidirectional"))
      (node (ref "U13") (pin "15") (pinfunction "A3_15") (pintype "input"))
    )
    (net (code "25") (name "BA1") (class "Default")
      (node (ref "CE0") (pin "24") (pinfunction "A1_24") (pintype "bidirectional"))
      (node (ref "U13") (pin "13") (pinfunction "A2_13") (pintype "input"))
    )
    (net (code "26") (name "BA2") (class "Default")
      (node (ref "CE0") (pin "25") (pinfunction "A2_25") (pintype "bidirectional"))
      (node (ref "U13") (pin "8") (pinfunction "A4_8") (pintype "input"))
    )
    (net (code "27") (name "BA3") (class "Default")
      (node (ref "CE0") (pin "26") (pinfunction "A3_26") (pintype "bidirectional"))
      (node (ref "U13") (pin "11") (pinfunction "A1_11") (pintype "input"))
    )
    (net (code "28") (name "BA4") (class "Default")
      (node (ref "CE0") (pin "27") (pinfunction "A4_27") (pintype "bidirectional"))
      (node (ref "U14") (pin "2") (pinfunction "A1_2") (pintype "input"))
    )
    (net (code "29") (name "BA5") (class "Default")
      (node (ref "CE0") (pin "28") (pinfunction "A5_28") (pintype "bidirectional"))
      (node (ref "U14") (pin "17") (pinfunction "A4_17") (pintype "input"))
    )
    (net (code "30") (name "BA6") (class "Default")
      (node (ref "CE0") (pin "29") (pinfunction "A6_29") (pintype "bidirectional"))
      (node (ref "U14") (pin "4") (pinfunction "A2_4") (pintype "input"))
    )
    (net (code "31") (name "BA7") (class "Default")
      (node (ref "CE0") (pin "30") (pinfunction "A7_30") (pintype "bidirectional"))
      (node (ref "U14") (pin "15") (pinfunction "A3_15") (pintype "input"))
    )
    (net (code "32") (name "BA8") (class "Default")
      (node (ref "CE0") (pin "31") (pinfunction "A8_31") (pintype "bidirectional"))
      (node (ref "U14") (pin "6") (pinfunction "A3_6") (pintype "input"))
    )
    (net (code "33") (name "BA9") (class "Default")
      (node (ref "CE0") (pin "32") (pinfunction "A9_32") (pintype "bidirectional"))
      (node (ref "U14") (pin "13") (pinfunction "A2_13") (pintype "input"))
    )
    (net (code "34") (name "BA10") (class "Default")
      (node (ref "CE0") (pin "33") (pinfunction "A10_33") (pintype "bidirectional"))
      (node (ref "U14") (pin "8") (pinfunction "A4_8") (pintype "input"))
    )
    (net (code "35") (name "BA11") (class "Default")
      (node (ref "CE0") (pin "34") (pinfunction "A11_34") (pintype "bidirectional"))
      (node (ref "U14") (pin "11") (pinfunction "A1_11") (pintype "input"))
    )
    (net (code "36") (name "BA12") (class "Default")
      (node (ref "CE0") (pin "35") (pinfunction "A12_35") (pintype "bidirectional"))
      (node (ref "U15") (pin "2") (pinfunction "A1_2") (pintype "input"))
    )
    (net (code "37") (name "BA13") (class "Default")
      (node (ref "CE0") (pin "36") (pinfunction "A13_36") (pintype "bidirectional"))
      (node (ref "U15") (pin "17") (pinfunction "A4_17") (pintype "input"))
    )
    (net (code "38") (name "BA14") (class "Default")
      (node (ref "CE0") (pin "37") (pinfunction "A14_37") (pintype "bidirectional"))
      (node (ref "U15") (pin "4") (pinfunction "A2_4") (pintype "input"))
    )
    (net (code "39") (name "BA15") (class "Default")
      (node (ref "CE0") (pin "38") (pinfunction "A15_38") (pintype "bidirectional"))
      (node (ref "U15") (pin "15") (pinfunction "A3_15") (pintype "input"))
    )
    (net (code "40") (name "BA16") (class "Default")
      (node (ref "CE0") (pin "39") (pinfunction "A16_39") (pintype "bidirectional"))
      (node (ref "U15") (pin "6") (pinfunction "A3_6") (pintype "input"))
    )
    (net (code "41") (name "BA17") (class "Default")
      (node (ref "CE0") (pin "40") (pinfunction "A17_40") (pintype "bidirectional"))
      (node (ref "U15") (pin "13") (pinfunction "A2_13") (pintype "input"))
    )
    (net (code "42") (name "BA18") (class "Default")
      (node (ref "CE0") (pin "41") (pinfunction "A18_41") (pintype "bidirectional"))
      (node (ref "U15") (pin "8") (pinfunction "A4_8") (pintype "input"))
    )
    (net (code "43") (name "BA19") (class "Default")
      (node (ref "CE0") (pin "42") (pinfunction "A19_42") (pintype "bidirectional"))
      (node (ref "U15") (pin "11") (pinfunction "A1_11") (pintype "input"))
    )
    (net (code "44") (name "D0") (class "Default")
      (node (ref "CF1") (pin "21") (pinfunction "D00_21") (pintype "tri_state"))
      (node (ref "RN2") (pin "2") (pinfunction "2_2") (pintype "passive"))
      (node (ref "U1") (pin "11") (pinfunction "D0_11") (pintype "tri_state"))
      (node (ref "U10") (pin "18") (pinfunction "Y1_18") (pintype "tri_state"))
      (node (ref "U16") (pin "18") (pinfunction "B1_18") (pintype "bidirectional"))
      (node (ref "U2") (pin "13") (pinfunction "D0_13") (pintype "tri_state"))
      (node (ref "U3") (pin "13") (pinfunction "D0_13") (pintype "tri_state"))
      (node (ref "U4") (pin "11") (pinfunction "D0_11") (pintype "tri_state"))
      (node (ref "U9") (pin "18") (pinfunction "Y1_18") (pintype "tri_state"))
    )
    (net (code "45") (name "D1") (class "Default")
      (node (ref "CF1") (pin "22") (pinfunction "D01_22") (pintype "tri_state"))
      (node (ref "RN2") (pin "3") (pinfunction "3_3") (pintype "passive"))
      (node (ref "U1") (pin "12") (pinfunction "D1_12") (pintype "tri_state"))
      (node (ref "U10") (pin "3") (pinfunction "Y4_3") (pintype "tri_state"))
      (node (ref "U16") (pin "17") (pinfunction "B2_17") (pintype "bidirectional"))
      (node (ref "U2") (pin "14") (pinfunction "D1_14") (pintype "tri_state"))
      (node (ref "U3") (pin "14") (pinfunction "D1_14") (pintype "tri_state"))
      (node (ref "U4") (pin "12") (pinfunction "D1_12") (pintype "tri_state"))
      (node (ref "U9") (pin "3") (pinfunction "Y4_3") (pintype "tri_state"))
    )
    (net (code "46") (name "D2") (class "Default")
      (node (ref "CF1") (pin "23") (pinfunction "D02_23") (pintype "tri_state"))
      (node (ref "RN2") (pin "4") (pinfunction "4_4") (pintype "passive"))
      (node (ref "U1") (pin "13") (pinfunction "D2_13") (pintype "tri_state"))
      (node (ref "U10") (pin "16") (pinfunction "Y2_16") (pintype "tri_state"))
      (node (ref "U16") (pin "16") (pinfunction "B3_16") (pintype "bidirectional"))
      (node (ref "U2") (pin "15") (pinfunction "D2_15") (pintype "tri_state"))
      (node (ref "U3") (pin "15") (pinfunction "D2_15") (pintype "tri_state"))
      (node (ref "U4") (pin "13") (pinfunction "D2_13") (pintype "tri_state"))
      (node (ref "U9") (pin "16") (pinfunction "Y2_16") (pintype "tri_state"))
    )
    (net (code "47") (name "D3") (class "Default")
      (node (ref "CF1") (pin "2") (pinfunction "D03_2") (pintype "tri_state"))
      (node (ref "RN2") (pin "5") (pinfunction "5_5") (pintype "passive"))
      (node (ref "U1") (pin "15") (pinfunction "D3_15") (pintype "tri_state"))
      (node (ref "U10") (pin "5") (pinfunction "Y3_5") (pintype "tri_state"))
      (node (ref "U16") (pin "15") (pinfunction "B4_15") (pintype "bidirectional"))
      (node (ref "U2") (pin "17") (pinfunction "D3_17") (pintype "tri_state"))
      (node (ref "U3") (pin "17") (pinfunction "D3_17") (pintype "tri_state"))
      (node (ref "U4") (pin "15") (pinfunction "D3_15") (pintype "tri_state"))
      (node (ref "U9") (pin "5") (pinfunction "Y3_5") (pintype "tri_state"))
    )
    (net (code "48") (name "D4") (class "Default")
      (node (ref "CF1") (pin "3") (pinfunction "D04_3") (pintype "tri_state"))
      (node (ref "RN2") (pin "6") (pinfunction "6_6") (pintype "passive"))
      (node (ref "U1") (pin "16") (pinfunction "D4_16") (pintype "tri_state"))
      (node (ref "U10") (pin "14") (pinfunction "Y3_14") (pintype "tri_state"))
      (node (ref "U16") (pin "14") (pinfunction "B5_14") (pintype "bidirectional"))
      (node (ref "U2") (pin "18") (pinfunction "D4_18") (pintype "tri_state"))
      (node (ref "U3") (pin "18") (pinfunction "D4_18") (pintype "tri_state"))
      (node (ref "U4") (pin "16") (pinfunction "D4_16") (pintype "tri_state"))
      (node (ref "U9") (pin "14") (pinfunction "Y3_14") (pintype "tri_state"))
    )
    (net (code "49") (name "D5") (class "Default")
      (node (ref "CF1") (pin "4") (pinfunction "D05_4") (pintype "tri_state"))
      (node (ref "RN2") (pin "7") (pinfunction "7_7") (pintype "passive"))
      (node (ref "U1") (pin "17") (pinfunction "D5_17") (pintype "tri_state"))
      (node (ref "U10") (pin "7") (pinfunction "Y2_7") (pintype "tri_state"))
      (node (ref "U16") (pin "13") (pinfunction "B6_13") (pintype "bidirectional"))
      (node (ref "U2") (pin "19") (pinfunction "D5_19") (pintype "tri_state"))
      (node (ref "U3") (pin "19") (pinfunction "D5_19") (pintype "tri_state"))
      (node (ref "U4") (pin "17") (pinfunction "D5_17") (pintype "tri_state"))
      (node (ref "U9") (pin "7") (pinfunction "Y2_7") (pintype "tri_state"))
    )
    (net (code "50") (name "D6") (class "Default")
      (node (ref "CF1") (pin "5") (pinfunction "D06_5") (pintype "tri_state"))
      (node (ref "RN2") (pin "8") (pinfunction "8_8") (pintype "passive"))
      (node (ref "U1") (pin "18") (pinfunction "D6_18") (pintype "tri_state"))
      (node (ref "U10") (pin "12") (pinfunction "Y4_12") (pintype "tri_state"))
      (node (ref "U16") (pin "12") (pinfunction "B7_12") (pintype "bidirectional"))
      (node (ref "U2") (pin "20") (pinfunction "D6_20") (pintype "tri_state"))
      (node (ref "U3") (pin "20") (pinfunction "D6_20") (pintype "tri_state"))
      (node (ref "U4") (pin "18") (pinfunction "D6_18") (pintype "tri_state"))
      (node (ref "U9") (pin "12") (pinfunction "Y4_12") (pintype "tri_state"))
    )
    (net (code "51") (name "D7") (class "Default")
      (node (ref "CF1") (pin "6") (pinfunction "D07_6") (pintype "tri_state"))
      (node (ref "RN2") (pin "9") (pinfunction "9_9") (pintype "passive"))
      (node (ref "U1") (pin "19") (pinfunction "D7_19") (pintype "tri_state"))
      (node (ref "U10") (pin "9") (pinfunction "Y1_9") (pintype "tri_state"))
      (node (ref "U16") (pin "11") (pinfunction "B8_11") (pintype "bidirectional"))
      (node (ref "U2") (pin "21") (pinfunction "D7_21") (pintype "tri_state"))
      (node (ref "U3") (pin "21") (pinfunction "D7_21") (pintype "tri_state"))
      (node (ref "U4") (pin "19") (pinfunction "D7_19") (pintype "tri_state"))
      (node (ref "U9") (pin "9") (pinfunction "Y1_9") (pintype "tri_state"))
    )
    (net (code "52") (name "GND") (class "Default")
      (node (ref "BT1") (pin "-") (pinfunction "-_-") (pintype "passive"))
      (node (ref "C1") (pin "2") (pinfunction "2_2") (pintype "passive"))
      (node (ref "C10") (pin "2") (pinfunction "2_2") (pintype "passive"))
      (node (ref "C11") (pin "2") (pinfunction "2_2") (pintype "passive"))
      (node (ref "C12") (pin "2") (pinfunction "2_2") (pintype "passive"))
      (node (ref "C13") (pin "2") (pinfunction "2_2") (pintype "passive"))
      (node (ref "C14") (pin "2") (pinfunction "2_2") (pintype "passive"))
      (node (ref "C15") (pin "2") (pinfunction "2_2") (pintype "passive"))
      (node (ref "C16") (pin "2") (pinfunction "2_2") (pintype "passive"))
      (node (ref "C17") (pin "2") (pinfunction "2_2") (pintype "passive"))
      (node (ref "C18") (pin "2") (pinfunction "2_2") (pintype "passive"))
      (node (ref "C19") (pin "-") (pinfunction "-_-") (pintype "passive"))
      (node (ref "C2") (pin "2") (pinfunction "2_2") (pintype "passive"))
      (node (ref "C3") (pin "2") (pinfunction "2_2") (pintype "passive"))
      (node (ref "C4") (pin "2") (pinfunction "2_2") (pintype "passive"))
      (node (ref "C5") (pin "2") (pinfunction "2_2") (pintype "passive"))
      (node (ref "C6") (pin "2") (pinfunction "2_2") (pintype "passive"))
      (node (ref "C7") (pin "2") (pinfunction "2_2") (pintype "passive"))
      (node (ref "C8") (pin "2") (pinfunction "2_2") (pintype "passive"))
      (node (ref "C9") (pin "2") (pinfunction "2_2") (pintype "passive"))
      (node (ref "CE0") (pin "3") (pinfunction "GND_3") (pintype "bidirectional"))
      (node (ref "CE0") (pin "4") (pinfunction "GND_4") (pintype "bidirectional"))
      (node (ref "CE0") (pin "62") (pinfunction "GND_62") (pintype "bidirectional"))
      (node (ref "CF1") (pin "10") (pinfunction "A09_10") (pintype "input"))
      (node (ref "CF1") (pin "11") (pinfunction "A08_11") (pintype "input"))
      (node (ref "CF1") (pin "12") (pinfunction "A07_12") (pintype "input"))
      (node (ref "CF1") (pin "14") (pinfunction "A06_14") (pintype "input"))
      (node (ref "CF1") (pin "15") (pinfunction "A05_15") (pintype "input"))
      (node (ref "CF1") (pin "16") (pinfunction "A04_16") (pintype "input"))
      (node (ref "CF1") (pin "17") (pinfunction "A03_17") (pintype "input"))
      (node (ref "CF1") (pin "39") (pinfunction "~{CSEL}_39") (pintype "input"))
      (node (ref "CF1") (pin "8") (pinfunction "A10_8") (pintype "input"))
      (node (ref "CF1") (pin "9") (pinfunction "~{ATASEL}_9") (pintype "input"))
      (node (ref "D1") (pin "K") (pinfunction "C_K") (pintype "passive"))
      (node (ref "R10") (pin "1") (pinfunction "1_1") (pintype "passive"))
      (node (ref "R7") (pin "1") (pinfunction "1_1") (pintype "passive"))
      (node (ref "R8") (pin "1") (pinfunction "1_1") (pintype "passive"))
      (node (ref "R9") (pin "1") (pinfunction "1_1") (pintype "passive"))
      (node (ref "RN1") (pin "1") (pinfunction "1_1") (pintype "passive"))
      (node (ref "U13") (pin "1") (pinfunction "G_1") (pintype "input"))
      (node (ref "U13") (pin "19") (pinfunction "G_19") (pintype "input"))
      (node (ref "U14") (pin "1") (pinfunction "G_1") (pintype "input"))
      (node (ref "U14") (pin "19") (pinfunction "G_19") (pintype "input"))
      (node (ref "U15") (pin "1") (pinfunction "G_1") (pintype "input"))
      (node (ref "U15") (pin "19") (pinfunction "G_19") (pintype "input"))
      (node (ref "U2") (pin "16") (pinfunction "GND_16") (pintype "power_in"))
    )
    (net (code "53") (name "ID0") (class "Default")
      (node (ref "U10") (pin "2") (pinfunction "A1_2") (pintype "input"))
    )
    (net (code "54") (name "ID1") (class "Default")
      (node (ref "U10") (pin "17") (pinfunction "A4_17") (pintype "input"))
    )
    (net (code "55") (name "ID2") (class "Default")
      (node (ref "U10") (pin "4") (pinfunction "A2_4") (pintype "input"))
    )
    (net (code "56") (name "ID3") (class "Default")
      (node (ref "U10") (pin "15") (pinfunction "A3_15") (pintype "input"))
    )
    (net (code "57") (name "ID4") (class "Default")
      (node (ref "U10") (pin "6") (pinfunction "A3_6") (pintype "input"))
    )
    (net (code "58") (name "ID5") (class "Default")
      (node (ref "U10") (pin "13") (pinfunction "A2_13") (pintype "input"))
    )
    (net (code "59") (name "ID6") (class "Default")
      (node (ref "U10") (pin "8") (pinfunction "A4_8") (pintype "input"))
    )
    (net (code "60") (name "ID7") (class "Default")
      (node (ref "U10") (pin "11") (pinfunction "A1_11") (pintype "input"))
    )
    (net (code "61") (name "INT_CF") (class "Default")
      (node (ref "CF1") (pin "37") (pinfunction "INTRQ_37") (pintype "output"))
      (node (ref "JP5") (pin "1") (pinfunction "1_1") (pintype "passive"))
    )
    (net (code "62") (name "Net-(CE0-D0)") (class "Default")
      (node (ref "CE0") (pin "43") (pinfunction "D0_43") (pintype "bidirectional"))
      (node (ref "U16") (pin "2") (pinfunction "A1_2") (pintype "bidirectional"))
    )
    (net (code "63") (name "Net-(CE0-D1)") (class "Default")
      (node (ref "CE0") (pin "44") (pinfunction "D1_44") (pintype "bidirectional"))
      (node (ref "U16") (pin "3") (pinfunction "A2_3") (pintype "bidirectional"))
    )
    (net (code "64") (name "Net-(CE0-D2)") (class "Default")
      (node (ref "CE0") (pin "45") (pinfunction "D2_45") (pintype "bidirectional"))
      (node (ref "U16") (pin "4") (pinfunction "A3_4") (pintype "bidirectional"))
    )
    (net (code "65") (name "Net-(CE0-D3)") (class "Default")
      (node (ref "CE0") (pin "46") (pinfunction "D3_46") (pintype "bidirectional"))
      (node (ref "U16") (pin "5") (pinfunction "A4_5") (pintype "bidirectional"))
    )
    (net (code "66") (name "Net-(CE0-D4)") (class "Default")
      (node (ref "CE0") (pin "47") (pinfunction "D4_47") (pintype "bidirectional"))
      (node (ref "U16") (pin "6") (pinfunction "A5_6") (pintype "bidirectional"))
    )
    (net (code "67") (name "Net-(CE0-D5)") (class "Default")
      (node (ref "CE0") (pin "48") (pinfunction "D5_48") (pintype "bidirectional"))
      (node (ref "U16") (pin "7") (pinfunction "A6_7") (pintype "bidirectional"))
    )
    (net (code "68") (name "Net-(CE0-D6)") (class "Default")
      (node (ref "CE0") (pin "49") (pinfunction "D6_49") (pintype "bidirectional"))
      (node (ref "U16") (pin "8") (pinfunction "A7_8") (pintype "bidirectional"))
    )
    (net (code "69") (name "Net-(CE0-D7)") (class "Default")
      (node (ref "CE0") (pin "50") (pinfunction "D7_50") (pintype "bidirectional"))
      (node (ref "U16") (pin "9") (pinfunction "A8_9") (pintype "bidirectional"))
    )
    (net (code "70") (name "Net-(CF1A-IORDY)") (class "Default")
      (node (ref "CF1") (pin "42") (pinfunction "IORDY_42") (pintype "output"))
      (node (ref "JP4") (pin "2") (pinfunction "2_2") (pintype "passive"))
    )
    (net (code "71") (name "Net-(CF1A-~{DASP})") (class "Default")
      (node (ref "CF1") (pin "45") (pinfunction "~{DASP}_45") (pintype "open_collector"))
      (node (ref "D2") (pin "C") (pinfunction "C_C") (pintype "passive"))
    )
    (net (code "72") (name "Net-(CF1A-~{PDIAG})") (class "Default")
      (node (ref "CF1") (pin "46") (pinfunction "~{PDIAG}_46") (pintype "output"))
      (node (ref "R12") (pin "1") (pinfunction "1_1") (pintype "passive"))
    )
    (net (code "73") (name "Net-(D1-PadA)") (class "Default")
      (node (ref "D1") (pin "A") (pinfunction "A_A") (pintype "passive"))
      (node (ref "R1") (pin "1") (pinfunction "1_1") (pintype "passive"))
    )
    (net (code "74") (name "Net-(D2-PadA)") (class "Default")
      (node (ref "D2") (pin "A") (pinfunction "A_A") (pintype "passive"))
      (node (ref "R11") (pin "1") (pinfunction "1_1") (pintype "passive"))
    )
    (net (code "75") (name "Net-(JP8-Pad1)") (class "Default")
      (node (ref "JP8") (pin "1") (pinfunction "1_1") (pintype "passive"))
      (node (ref "R8") (pin "2") (pinfunction "2_2") (pintype "passive"))
      (node (ref "S2") (pin "3") (pinfunction "3_3") (pintype "passive"))
    )
    (net (code "76") (name "Net-(JP10-Pad1)") (class "Default")
      (node (ref "JP10") (pin "1") (pinfunction "1_1") (pintype "passive"))
      (node (ref "R9") (pin "2") (pinfunction "2_2") (pintype "passive"))
      (node (ref "S2") (pin "2") (pinfunction "2_2") (pintype "passive"))
    )
    (net (code "77") (name "Net-(JP12-Pad1)") (class "Default")
      (node (ref "JP12") (pin "1") (pinfunction "1_1") (pintype "passive"))
      (node (ref "R10") (pin "2") (pinfunction "2_2") (pintype "passive"))
      (node (ref "S2") (pin "1") (pinfunction "1_1") (pintype "passive"))
    )
    (net (code "78") (name "Net-(Q1-B)") (class "Default")
      (node (ref "Q1") (pin "2") (pinfunction "B_2") (pintype "passive"))
      (node (ref "R2") (pin "2") (pinfunction "2_2") (pintype "passive"))
    )
    (net (code "79") (name "Net-(Q1-C)") (class "Default")
      (node (ref "Q1") (pin "3") (pinfunction "C_3") (pintype "passive"))
      (node (ref "R1") (pin "2") (pinfunction "2_2") (pintype "passive"))
    )
    (net (code "80") (name "Net-(U1A-A12)") (class "Default")
      (node (ref "JP8") (pin "2") (pinfunction "2_2") (pintype "passive"))
      (node (ref "U1") (pin "2") (pinfunction "A12_2") (pintype "input"))
    )
    (net (code "81") (name "Net-(U1A-A13)") (class "Default")
      (node (ref "JP10") (pin "2") (pinfunction "2_2") (pintype "passive"))
      (node (ref "U1") (pin "26") (pinfunction "A13_26") (pintype "input"))
    )
    (net (code "82") (name "Net-(U1A-A14)") (class "Default")
      (node (ref "JP12") (pin "2") (pinfunction "2_2") (pintype "passive"))
      (node (ref "U1") (pin "1") (pinfunction "A14_1") (pintype "input"))
    )
    (net (code "83") (name "Net-(U2A-~{CE})") (class "Default")
      (node (ref "JP6") (pin "2") (pinfunction "2_2") (pintype "passive"))
      (node (ref "U2") (pin "22") (pinfunction "~{CE}_22") (pintype "input"))
    )
    (net (code "84") (name "Net-(U2B-VCC)") (class "Default")
      (node (ref "C2") (pin "1") (pinfunction "1_1") (pintype "passive"))
      (node (ref "JP7") (pin "2") (pinfunction "2_2") (pintype "passive"))
      (node (ref "U2") (pin "32") (pinfunction "VCC_32") (pintype "power_in"))
    )
    (net (code "85") (name "Net-(U3A-~{CE})") (class "Default")
      (node (ref "U3") (pin "22") (pinfunction "~{CE}_22") (pintype "input"))
      (node (ref "U7") (pin "6") (pinfunction "O_6") (pintype "output"))
    )
    (net (code "86") (name "Net-(U4A-BC)") (class "Default")
      (node (ref "BT1") (pin "+") (pinfunction "+_+") (pintype "passive"))
      (node (ref "U4") (pin "24") (pinfunction "BC_24") (pintype "input"))
    )
    (net (code "87") (name "Net-(U4A-VCC)") (class "Default")
      (node (ref "C4") (pin "1") (pinfunction "1_1") (pintype "passive"))
      (node (ref "JP14") (pin "2") (pinfunction "2_2") (pintype "passive"))
      (node (ref "U4") (pin "28") (pinfunction "VCC_28") (pintype "input"))
    )
    (net (code "88") (name "Net-(U4A-WDI)") (class "Default")
      (node (ref "JP1") (pin "2") (pinfunction "2_2") (pintype "passive"))
      (node (ref "U4") (pin "23") (pinfunction "WDI_23") (pintype "input"))
    )
    (net (code "89") (name "Net-(U4A-X1)") (class "Default")
      (node (ref "U4") (pin "2") (pinfunction "X1_2") (pintype "input"))
      (node (ref "Y1") (pin "2") (pinfunction "2_2") (pintype "passive"))
    )
    (net (code "90") (name "Net-(U4A-X2)") (class "Default")
      (node (ref "U4") (pin "3") (pinfunction "X2_3") (pintype "input"))
      (node (ref "Y1") (pin "1") (pinfunction "1_1") (pintype "passive"))
    )
    (net (code "91") (name "Net-(U4A-~{RST})") (class "Default")
      (node (ref "JP2") (pin "1") (pinfunction "1_1") (pintype "passive"))
      (node (ref "U4") (pin "6") (pinfunction "~{RST}_6") (pintype "open_collector"))
    )
    (net (code "92") (name "Net-(U4A-~{WDO})") (class "Default")
      (node (ref "R2") (pin "1") (pinfunction "1_1") (pintype "passive"))
      (node (ref "U4") (pin "4") (pinfunction "~{WDO}_4") (pintype "output"))
    )
    (net (code "93") (name "Net-(U5A-G)") (class "Default")
      (node (ref "U5") (pin "1") (pinfunction "G_1") (pintype "input"))
      (node (ref "U8") (pin "2") (pinfunction "O_2") (pintype "output"))
    )
    (net (code "94") (name "Net-(U5A-P0)") (class "Default")
      (node (ref "JP9") (pin "2") (pinfunction "2_2") (pintype "passive"))
      (node (ref "U5") (pin "2") (pinfunction "P0_2") (pintype "input"))
    )
    (net (code "95") (name "Net-(U5A-P1)") (class "Default")
      (node (ref "JP13") (pin "2") (pinfunction "2_2") (pintype "passive"))
      (node (ref "U5") (pin "4") (pinfunction "P1_4") (pintype "input"))
    )
    (net (code "96") (name "Net-(U5A-P7)") (class "Default")
      (node (ref "JP11") (pin "2") (pinfunction "2_2") (pintype "passive"))
      (node (ref "U5") (pin "17") (pinfunction "P7_17") (pintype "input"))
    )
    (net (code "97") (name "Net-(U6A-I0)") (class "Default")
      (node (ref "U6") (pin "1") (pinfunction "I0_1") (pintype "input"))
      (node (ref "U8") (pin "12") (pinfunction "O_12") (pintype "output"))
    )
    (net (code "98") (name "Net-(U7A-I0)") (class "Default")
      (node (ref "U7") (pin "1") (pinfunction "I0_1") (pintype "input"))
      (node (ref "U8") (pin "6") (pinfunction "O_6") (pintype "output"))
    )
    (net (code "99") (name "Net-(U7C-O)") (class "Default")
      (node (ref "U7") (pin "8") (pinfunction "O_8") (pintype "output"))
      (node (ref "U8") (pin "9") (pinfunction "I_9") (pintype "input"))
    )
    (net (code "100") (name "Net-(U8B-I)") (class "Default")
      (node (ref "JP5") (pin "2") (pinfunction "2_2") (pintype "passive"))
      (node (ref "R7") (pin "2") (pinfunction "2_2") (pintype "passive"))
      (node (ref "U8") (pin "3") (pinfunction "I_3") (pintype "input"))
    )
    (net (code "101") (name "Net-(U16A-G)") (class "Default")
      (node (ref "U16") (pin "19") (pinfunction "G_19") (pintype "input"))
      (node (ref "U6") (pin "3") (pinfunction "O_3") (pintype "output"))
    )
    (net (code "102") (name "SW12") (class "Default")
      (node (ref "JP9") (pin "3") (pinfunction "3_3") (pintype "passive"))
      (node (ref "RN1") (pin "2") (pinfunction "2_2") (pintype "passive"))
      (node (ref "S1") (pin "8") (pinfunction "8_8") (pintype "passive"))
      (node (ref "U5") (pin "3") (pinfunction "Q0_3") (pintype "input"))
    )
    (net (code "103") (name "SW13") (class "Default")
      (node (ref "JP11") (pin "3") (pinfunction "3_3") (pintype "passive"))
      (node (ref "RN1") (pin "3") (pinfunction "3_3") (pintype "passive"))
      (node (ref "S1") (pin "7") (pinfunction "7_7") (pintype "passive"))
      (node (ref "U5") (pin "18") (pinfunction "Q7_18") (pintype "input"))
    )
    (net (code "104") (name "SW14") (class "Default")
      (node (ref "JP13") (pin "3") (pinfunction "3_3") (pintype "passive"))
      (node (ref "RN1") (pin "4") (pinfunction "4_4") (pintype "passive"))
      (node (ref "S1") (pin "6") (pinfunction "6_6") (pintype "passive"))
      (node (ref "U5") (pin "5") (pinfunction "Q1_5") (pintype "input"))
    )
    (net (code "105") (name "SW15") (class "Default")
      (node (ref "RN1") (pin "5") (pinfunction "5_5") (pintype "passive"))
      (node (ref "S1") (pin "5") (pinfunction "5_5") (pintype "passive"))
      (node (ref "U5") (pin "16") (pinfunction "Q6_16") (pintype "input"))
    )
    (net (code "106") (name "SW16") (class "Default")
      (node (ref "RN1") (pin "6") (pinfunction "6_6") (pintype "passive"))
      (node (ref "S1") (pin "4") (pinfunction "4_4") (pintype "passive"))
      (node (ref "U5") (pin "7") (pinfunction "Q2_7") (pintype "input"))
    )
    (net (code "107") (name "SW17") (class "Default")
      (node (ref "RN1") (pin "7") (pinfunction "7_7") (pintype "passive"))
      (node (ref "S1") (pin "3") (pinfunction "3_3") (pintype "passive"))
      (node (ref "U5") (pin "14") (pinfunction "Q5_14") (pintype "input"))
    )
    (net (code "108") (name "SW18") (class "Default")
      (node (ref "RN1") (pin "8") (pinfunction "8_8") (pintype "passive"))
      (node (ref "S1") (pin "2") (pinfunction "2_2") (pintype "passive"))
      (node (ref "U5") (pin "9") (pinfunction "Q3_9") (pintype "input"))
    )
    (net (code "109") (name "SW19") (class "Default")
      (node (ref "RN1") (pin "9") (pinfunction "9_9") (pintype "passive"))
      (node (ref "S1") (pin "1") (pinfunction "1_1") (pintype "passive"))
      (node (ref "U5") (pin "12") (pinfunction "Q4_12") (pintype "input"))
    )
    (net (code "110") (name "VBAT") (class "Default")
      (node (ref "JP7") (pin "3") (pinfunction "3_3") (pintype "passive"))
      (node (ref "U4") (pin "1") (pinfunction "VOUT_1") (pintype "input"))
    )
    (net (code "111") (name "VCC") (class "Default")
      (node (ref "C1") (pin "1") (pinfunction "1_1") (pintype "passive"))
      (node (ref "C10") (pin "1") (pinfunction "1_1") (pintype "passive"))
      (node (ref "C11") (pin "1") (pinfunction "1_1") (pintype "passive"))
      (node (ref "C12") (pin "1") (pinfunction "1_1") (pintype "passive"))
      (node (ref "C13") (pin "1") (pinfunction "1_1") (pintype "passive"))
      (node (ref "C14") (pin "1") (pinfunction "1_1") (pintype "passive"))
      (node (ref "C15") (pin "1") (pinfunction "1_1") (pintype "passive"))
      (node (ref "C16") (pin "1") (pinfunction "1_1") (pintype "passive"))
      (node (ref "C17") (pin "1") (pinfunction "1_1") (pintype "passive"))
      (node (ref "C18") (pin "1") (pinfunction "1_1") (pintype "passive"))
      (node (ref "C19") (pin "+") (pinfunction "+_+") (pintype "passive"))
      (node (ref "C3") (pin "1") (pinfunction "1_1") (pintype "passive"))
      (node (ref "C5") (pin "1") (pinfunction "1_1") (pintype "passive"))
      (node (ref "C6") (pin "1") (pinfunction "1_1") (pintype "passive"))
      (node (ref "C7") (pin "1") (pinfunction "1_1") (pintype "passive"))
      (node (ref "C8") (pin "1") (pinfunction "1_1") (pintype "passive"))
      (node (ref "C9") (pin "1") (pinfunction "1_1") (pintype "passive"))
      (node (ref "CE0") (pin "5") (pinfunction "+5V_5") (pintype "bidirectional"))
      (node (ref "CE0") (pin "6") (pinfunction "+5V_6") (pintype "bidirectional"))
      (node (ref "CF1") (pin "32") (pinfunction "~{CS1}_32") (pintype "input"))
      (node (ref "CF1") (pin "36") (pinfunction "~{WE}_36") (pintype "input"))
      (node (ref "CF1") (pin "44") (pinfunction "~{DMACK}_44") (pintype "input"))
      (node (ref "JP14") (pin "3") (pinfunction "3_3") (pintype "passive"))
      (node (ref "JP7") (pin "1") (pinfunction "1_1") (pintype "passive"))
      (node (ref "Q1") (pin "1") (pinfunction "E_1") (pintype "passive"))
      (node (ref "R11") (pin "2") (pinfunction "2_2") (pintype "passive"))
      (node (ref "R12") (pin "2") (pinfunction "2_2") (pintype "passive"))
      (node (ref "R3") (pin "1") (pinfunction "1_1") (pintype "passive"))
      (node (ref "R4") (pin "2") (pinfunction "2_2") (pintype "passive"))
      (node (ref "R5") (pin "1") (pinfunction "1_1") (pintype "passive"))
      (node (ref "R6") (pin "1") (pinfunction "1_1") (pintype "passive"))
      (node (ref "RN2") (pin "1") (pinfunction "1_1") (pintype "passive"))
      (node (ref "S1") (pin "10") (pinfunction "10_10") (pintype "passive"))
      (node (ref "S1") (pin "11") (pinfunction "11_11") (pintype "passive"))
      (node (ref "S1") (pin "12") (pinfunction "12_12") (pintype "passive"))
      (node (ref "S1") (pin "13") (pinfunction "13_13") (pintype "passive"))
      (node (ref "S1") (pin "14") (pinfunction "14_14") (pintype "passive"))
      (node (ref "S1") (pin "15") (pinfunction "15_15") (pintype "passive"))
      (node (ref "S1") (pin "16") (pinfunction "16_16") (pintype "passive"))
      (node (ref "S1") (pin "9") (pinfunction "9_9") (pintype "passive"))
      (node (ref "S2") (pin "4") (pinfunction "4_4") (pintype "passive"))
      (node (ref "S2") (pin "5") (pinfunction "5_5") (pintype "passive"))
      (node (ref "S2") (pin "6") (pinfunction "6_6") (pintype "passive"))
      (node (ref "U1") (pin "27") (pinfunction "~{WE}_27") (pintype "input"))
      (node (ref "U11") (pin "6") (pinfunction "G1_6") (pintype "input"))
      (node (ref "U13") (pin "2") (pinfunction "A1_2") (pintype "input"))
      (node (ref "U6") (pin "10") (pinfunction "I1_10") (pintype "input"))
      (node (ref "U6") (pin "12") (pinfunction "I0_12") (pintype "input"))
      (node (ref "U6") (pin "13") (pinfunction "I1_13") (pintype "input"))
      (node (ref "U6") (pin "4") (pinfunction "I0_4") (pintype "input"))
      (node (ref "U6") (pin "5") (pinfunction "I1_5") (pintype "input"))
      (node (ref "U6") (pin "9") (pinfunction "I0_9") (pintype "input"))
      (node (ref "U7") (pin "9") (pinfunction "I0_9") (pintype "input"))
      (node (ref "U8") (pin "11") (pinfunction "I_11") (pintype "input"))
      (node (ref "U9") (pin "11") (pinfunction "A1_11") (pintype "input"))
      (node (ref "U9") (pin "13") (pinfunction "A2_13") (pintype "input"))
      (node (ref "U9") (pin "6") (pinfunction "A3_6") (pintype "input"))
      (node (ref "U9") (pin "8") (pinfunction "A4_8") (pintype "input"))
    )
    (net (code "112") (name "unconnected-(CE0-+3.3V-Pad2)") (class "Default")
      (node (ref "CE0") (pin "2") (pinfunction "+3.3V_2") (pintype "bidirectional"))
    )
    (net (code "113") (name "unconnected-(CE0-+12V-Pad1)") (class "Default")
      (node (ref "CE0") (pin "1") (pinfunction "+12V_1") (pintype "bidirectional"))
    )
    (net (code "114") (name "unconnected-(CE0--12V-Pad7)") (class "Default")
      (node (ref "CE0") (pin "7") (pinfunction "-12V_7") (pintype "bidirectional"))
    )
    (net (code "115") (name "unconnected-(CE0-CLK-Pad15)") (class "Default")
      (node (ref "CE0") (pin "15") (pinfunction "CLK_15") (pintype "bidirectional"))
    )
    (net (code "116") (name "unconnected-(CE0-CLKAUX-Pad16)") (class "Default")
      (node (ref "CE0") (pin "16") (pinfunction "CLKAUX_16") (pintype "bidirectional"))
    )
    (net (code "117") (name "unconnected-(CE0-~{BUSACK}-Pad20)") (class "Default")
      (node (ref "CE0") (pin "20") (pinfunction "~{BUSACK}_20") (pintype "bidirectional"))
    )
    (net (code "118") (name "unconnected-(CE0-~{BUSRQ}-Pad10)") (class "Default")
      (node (ref "CE0") (pin "10") (pinfunction "~{BUSRQ}_10") (pintype "bidirectional"))
    )
    (net (code "119") (name "unconnected-(CE0-~{CBR}-Pad12)") (class "Default")
      (node (ref "CE0") (pin "12") (pinfunction "~{CBR}_12") (pintype "bidirectional"))
    )
    (net (code "120") (name "unconnected-(CE0-~{FETCH}-Pad19)") (class "Default")
      (node (ref "CE0") (pin "19") (pinfunction "~{FETCH}_19") (pintype "bidirectional"))
    )
    (net (code "121") (name "unconnected-(CE0-~{HALT}-Pad17)") (class "Default")
      (node (ref "CE0") (pin "17") (pinfunction "~{HALT}_17") (pintype "bidirectional"))
    )
    (net (code "122") (name "unconnected-(CE0-~{INH}-Pad11)") (class "Default")
      (node (ref "CE0") (pin "11") (pinfunction "~{INH}_11") (pintype "bidirectional"))
    )
    (net (code "123") (name "unconnected-(CE0-~{INT}-Pad51)") (class "Default")
      (node (ref "CE0") (pin "51") (pinfunction "~{INT}_51") (pintype "bidirectional"))
    )
    (net (code "124") (name "unconnected-(CE0-~{IRQ0}-Pad53)") (class "Default")
      (node (ref "CE0") (pin "53") (pinfunction "~{IRQ0}_53") (pintype "bidirectional"))
    )
    (net (code "125") (name "unconnected-(CE0-~{IRQ1}-Pad54)") (class "Default")
      (node (ref "CE0") (pin "54") (pinfunction "~{IRQ1}_54") (pintype "bidirectional"))
    )
    (net (code "126") (name "unconnected-(CE0-~{IRQ2}-Pad55)") (class "Default")
      (node (ref "CE0") (pin "55") (pinfunction "~{IRQ2}_55") (pintype "bidirectional"))
    )
    (net (code "127") (name "unconnected-(CE0-~{IRQ3}-Pad56)") (class "Default")
      (node (ref "CE0") (pin "56") (pinfunction "~{IRQ3}_56") (pintype "bidirectional"))
    )
    (net (code "128") (name "unconnected-(CE0-~{IRQ4}-Pad57)") (class "Default")
      (node (ref "CE0") (pin "57") (pinfunction "~{IRQ4}_57") (pintype "bidirectional"))
    )
    (net (code "129") (name "unconnected-(CE0-~{IRQ5}-Pad58)") (class "Default")
      (node (ref "CE0") (pin "58") (pinfunction "~{IRQ5}_58") (pintype "bidirectional"))
    )
    (net (code "130") (name "unconnected-(CE0-~{IRQ6}-Pad59)") (class "Default")
      (node (ref "CE0") (pin "59") (pinfunction "~{IRQ6}_59") (pintype "bidirectional"))
    )
    (net (code "131") (name "unconnected-(CE0-~{IRQ7}-Pad60)") (class "Default")
      (node (ref "CE0") (pin "60") (pinfunction "~{IRQ7}_60") (pintype "bidirectional"))
    )
    (net (code "132") (name "unconnected-(CE0-~{NMI}-Pad61)") (class "Default")
      (node (ref "CE0") (pin "61") (pinfunction "~{NMI}_61") (pintype "bidirectional"))
    )
    (net (code "133") (name "unconnected-(CF1A-D08-Pad47)") (class "Default")
      (node (ref "CF1") (pin "47") (pinfunction "D08_47") (pintype "tri_state"))
    )
    (net (code "134") (name "unconnected-(CF1A-D09-Pad48)") (class "Default")
      (node (ref "CF1") (pin "48") (pinfunction "D09_48") (pintype "tri_state"))
    )
    (net (code "135") (name "unconnected-(CF1A-D10-Pad49)") (class "Default")
      (node (ref "CF1") (pin "49") (pinfunction "D10_49") (pintype "tri_state"))
    )
    (net (code "136") (name "unconnected-(CF1A-D11-Pad27)") (class "Default")
      (node (ref "CF1") (pin "27") (pinfunction "D11_27") (pintype "tri_state"))
    )
    (net (code "137") (name "unconnected-(CF1A-D12-Pad28)") (class "Default")
      (node (ref "CF1") (pin "28") (pinfunction "D12_28") (pintype "tri_state"))
    )
    (net (code "138") (name "unconnected-(CF1A-D13-Pad29)") (class "Default")
      (node (ref "CF1") (pin "29") (pinfunction "D13_29") (pintype "tri_state"))
    )
    (net (code "139") (name "unconnected-(CF1A-D14-Pad30)") (class "Default")
      (node (ref "CF1") (pin "30") (pinfunction "D14_30") (pintype "tri_state"))
    )
    (net (code "140") (name "unconnected-(CF1A-D15-Pad31)") (class "Default")
      (node (ref "CF1") (pin "31") (pinfunction "D15_31") (pintype "tri_state"))
    )
    (net (code "141") (name "unconnected-(CF1A-DMARQ-Pad43)") (class "Default")
      (node (ref "CF1") (pin "43") (pinfunction "DMARQ_43") (pintype "output"))
    )
    (net (code "142") (name "unconnected-(CF1A-~{IOCS16}-Pad24)") (class "Default")
      (node (ref "CF1") (pin "24") (pinfunction "~{IOCS16}_24") (pintype "output"))
    )
    (net (code "143") (name "unconnected-(CF1A-~{VS1}-Pad33)") (class "Default")
      (node (ref "CF1") (pin "33") (pinfunction "~{VS1}_33") (pintype "output"))
    )
    (net (code "144") (name "unconnected-(CF1A-~{VS2}-Pad40)") (class "Default")
      (node (ref "CF1") (pin "40") (pinfunction "~{VS2}_40") (pintype "output"))
    )
    (net (code "145") (name "unconnected-(U6B-O-Pad6)") (class "Default")
      (node (ref "U6") (pin "6") (pinfunction "O_6") (pintype "output"))
    )
    (net (code "146") (name "unconnected-(U6C-O-Pad8)") (class "Default")
      (node (ref "U6") (pin "8") (pinfunction "O_8") (pintype "output"))
    )
    (net (code "147") (name "unconnected-(U6D-O-Pad11)") (class "Default")
      (node (ref "U6") (pin "11") (pinfunction "O_11") (pintype "output"))
    )
    (net (code "148") (name "unconnected-(U8E-O-Pad10)") (class "Default")
      (node (ref "U8") (pin "10") (pinfunction "O_10") (pintype "output"))
    )
    (net (code "149") (name "unconnected-(U11A-Y2-Pad13)") (class "Default")
      (node (ref "U11") (pin "13") (pinfunction "Y2_13") (pintype "output"))
    )
    (net (code "150") (name "unconnected-(U11A-Y3-Pad12)") (class "Default")
      (node (ref "U11") (pin "12") (pinfunction "Y3_12") (pintype "output"))
    )
    (net (code "151") (name "unconnected-(U11A-Y4-Pad11)") (class "Default")
      (node (ref "U11") (pin "11") (pinfunction "Y4_11") (pintype "output"))
    )
    (net (code "152") (name "unconnected-(U11A-Y5-Pad10)") (class "Default")
      (node (ref "U11") (pin "10") (pinfunction "Y5_10") (pintype "output"))
    )
    (net (code "153") (name "unconnected-(U11A-Y6-Pad9)") (class "Default")
      (node (ref "U11") (pin "9") (pinfunction "Y6_9") (pintype "output"))
    )
    (net (code "154") (name "unconnected-(U11A-Y7-Pad7)") (class "Default")
      (node (ref "U11") (pin "7") (pinfunction "Y7_7") (pintype "output"))
    )
    (net (code "155") (name "unconnected-(U12A-Y0-Pad15)") (class "Default")
      (node (ref "U12") (pin "15") (pinfunction "Y0_15") (pintype "output"))
    )
    (net (code "156") (name "unconnected-(U12A-Y1-Pad14)") (class "Default")
      (node (ref "U12") (pin "14") (pinfunction "Y1_14") (pintype "output"))
    )
    (net (code "157") (name "unconnected-(U12A-Y2-Pad13)") (class "Default")
      (node (ref "U12") (pin "13") (pinfunction "Y2_13") (pintype "output"))
    )
    (net (code "158") (name "unconnected-(U12A-Y3-Pad12)") (class "Default")
      (node (ref "U12") (pin "12") (pinfunction "Y3_12") (pintype "output"))
    )
    (net (code "159") (name "unconnected-(U12A-Y5-Pad10)") (class "Default")
      (node (ref "U12") (pin "10") (pinfunction "Y5_10") (pintype "output"))
    )
    (net (code "160") (name "unconnected-(U12A-Y6-Pad9)") (class "Default")
      (node (ref "U12") (pin "9") (pinfunction "Y6_9") (pintype "output"))
    )
    (net (code "161") (name "unconnected-(U13A-Y1-Pad18)") (class "Default")
      (node (ref "U13") (pin "18") (pinfunction "Y1_18") (pintype "tri_state"))
    )
    (net (code "162") (name "~{BCSX}") (class "Default")
      (node (ref "CE0") (pin "9") (pinfunction "~{CSX}_9") (pintype "bidirectional"))
      (node (ref "U13") (pin "17") (pinfunction "A4_17") (pintype "input"))
    )
    (net (code "163") (name "~{BRD}") (class "Default")
      (node (ref "CE0") (pin "21") (pinfunction "~{RD}_21") (pintype "bidirectional"))
      (node (ref "U13") (pin "4") (pinfunction "A2_4") (pintype "input"))
    )
    (net (code "164") (name "~{BWR}") (class "Default")
      (node (ref "CE0") (pin "22") (pinfunction "~{WR}_22") (pintype "bidirectional"))
      (node (ref "U13") (pin "6") (pinfunction "A3_6") (pintype "input"))
    )
    (net (code "165") (name "~{CESB}IN") (class "Default")
      (node (ref "JP6") (pin "1") (pinfunction "1_1") (pintype "passive"))
      (node (ref "U4") (pin "26") (pinfunction "~{CEIN}_26") (pintype "input"))
      (node (ref "U7") (pin "12") (pinfunction "O_12") (pintype "output"))
    )
    (net (code "166") (name "~{CESB}OUT") (class "Default")
      (node (ref "JP6") (pin "3") (pinfunction "3_3") (pintype "passive"))
      (node (ref "U4") (pin "25") (pinfunction "~{CEOUT}_25") (pintype "output"))
    )
    (net (code "167") (name "~{CF_CD1}") (class "Default")
      (node (ref "CF1") (pin "26") (pinfunction "~{CD1}_26") (pintype "output"))
      (node (ref "R6") (pin "2") (pinfunction "2_2") (pintype "passive"))
      (node (ref "U9") (pin "4") (pinfunction "A2_4") (pintype "input"))
    )
    (net (code "168") (name "~{CF_CD2}") (class "Default")
      (node (ref "CF1") (pin "25") (pinfunction "~{CD2}_25") (pintype "output"))
      (node (ref "R5") (pin "2") (pinfunction "2_2") (pintype "passive"))
      (node (ref "U9") (pin "15") (pinfunction "A3_15") (pintype "input"))
    )
    (net (code "169") (name "~{CINH}") (class "Default")
      (node (ref "CE0") (pin "13") (pinfunction "~{CINH}_13") (pintype "bidirectional"))
      (node (ref "U7") (pin "13") (pinfunction "I2_13") (pintype "input"))
      (node (ref "U7") (pin "5") (pinfunction "I2_5") (pintype "input"))
      (node (ref "U8") (pin "1") (pinfunction "I_1") (pintype "input"))
      (node (ref "U8") (pin "13") (pinfunction "I_13") (pintype "input"))
    )
    (net (code "170") (name "~{CSX}") (class "Default")
      (node (ref "U11") (pin "4") (pinfunction "G2A_4") (pintype "input"))
      (node (ref "U12") (pin "4") (pinfunction "G2A_4") (pintype "input"))
      (node (ref "U13") (pin "3") (pinfunction "Y4_3") (pintype "tri_state"))
      (node (ref "U6") (pin "2") (pinfunction "I1_2") (pintype "input"))
    )
    (net (code "171") (name "~{CS_CF}") (class "Default")
      (node (ref "CF1") (pin "7") (pinfunction "~{CS0}_7") (pintype "input"))
      (node (ref "U11") (pin "15") (pinfunction "Y0_15") (pintype "output"))
    )
    (net (code "172") (name "~{CS_ID}") (class "Default")
      (node (ref "U10") (pin "1") (pinfunction "G_1") (pintype "input"))
      (node (ref "U10") (pin "19") (pinfunction "G_19") (pintype "input"))
      (node (ref "U12") (pin "7") (pinfunction "Y7_7") (pintype "output"))
    )
    (net (code "173") (name "~{CS_RTC}") (class "Default")
      (node (ref "U11") (pin "14") (pinfunction "Y1_14") (pintype "output"))
      (node (ref "U4") (pin "21") (pinfunction "~{CS}_21") (pintype "input"))
    )
    (net (code "174") (name "~{CS_SR}") (class "Default")
      (node (ref "U12") (pin "11") (pinfunction "Y4_11") (pintype "output"))
      (node (ref "U9") (pin "1") (pinfunction "G_1") (pintype "input"))
      (node (ref "U9") (pin "19") (pinfunction "G_19") (pintype "input"))
    )
    (net (code "175") (name "~{INT_RTC}") (class "Default")
      (node (ref "JP3") (pin "1") (pinfunction "1_1") (pintype "passive"))
      (node (ref "U4") (pin "5") (pinfunction "~{INT}_5") (pintype "open_collector"))
    )
    (net (code "176") (name "~{IRQX}") (class "Default")
      (node (ref "CE0") (pin "52") (pinfunction "~{IRQX}_52") (pintype "bidirectional"))
      (node (ref "U8") (pin "8") (pinfunction "O_8") (pintype "output"))
    )
    (net (code "177") (name "~{RD}") (class "Default")
      (node (ref "CF1") (pin "34") (pinfunction "~{IORD}_34") (pintype "input"))
      (node (ref "U1") (pin "22") (pinfunction "~{OE}_22") (pintype "input"))
      (node (ref "U12") (pin "5") (pinfunction "G2B_5") (pintype "input"))
      (node (ref "U13") (pin "16") (pinfunction "Y2_16") (pintype "tri_state"))
      (node (ref "U16") (pin "1") (pinfunction "DIR_1") (pintype "input"))
      (node (ref "U2") (pin "24") (pinfunction "~{OE}_24") (pintype "input"))
      (node (ref "U3") (pin "24") (pinfunction "~{OE}_24") (pintype "input"))
      (node (ref "U4") (pin "22") (pinfunction "~{OE}_22") (pintype "input"))
    )
    (net (code "178") (name "~{RST}") (class "Default")
      (node (ref "CE0") (pin "14") (pinfunction "~{RST}_14") (pintype "bidirectional"))
      (node (ref "CF1") (pin "41") (pinfunction "/RESET_41") (pintype "input"))
      (node (ref "JP2") (pin "2") (pinfunction "2_2") (pintype "passive"))
    )
    (net (code "179") (name "~{SR_CF}") (class "Default")
      (node (ref "U7") (pin "11") (pinfunction "I2_11") (pintype "input"))
      (node (ref "U8") (pin "4") (pinfunction "O_4") (pintype "output"))
      (node (ref "U9") (pin "2") (pinfunction "A1_2") (pintype "input"))
    )
    (net (code "180") (name "~{SR_RTC}") (class "Default")
      (node (ref "JP3") (pin "2") (pinfunction "2_2") (pintype "passive"))
      (node (ref "R4") (pin "1") (pinfunction "1_1") (pintype "passive"))
      (node (ref "U7") (pin "10") (pinfunction "I1_10") (pintype "input"))
      (node (ref "U9") (pin "17") (pinfunction "A4_17") (pintype "input"))
    )
    (net (code "181") (name "~{U3CS}") (class "Default")
      (node (ref "R3") (pin "2") (pinfunction "2_2") (pintype "passive"))
      (node (ref "U1") (pin "20") (pinfunction "~{CE}_20") (pintype "input"))
      (node (ref "U5") (pin "19") (pinfunction "P=Q_19") (pintype "output"))
      (node (ref "U7") (pin "2") (pinfunction "I1_2") (pintype "input"))
      (node (ref "U7") (pin "4") (pinfunction "I1_4") (pintype "input"))
    )
    (net (code "182") (name "~{WAIT}") (class "Default")
      (node (ref "CE0") (pin "18") (pinfunction "~{WAIT}_18") (pintype "bidirectional"))
      (node (ref "JP4") (pin "1") (pinfunction "1_1") (pintype "passive"))
    )
    (net (code "183") (name "~{WR}") (class "Default")
      (node (ref "CF1") (pin "35") (pinfunction "~{IOWR}_35") (pintype "input"))
      (node (ref "U13") (pin "14") (pinfunction "Y3_14") (pintype "tri_state"))
      (node (ref "U2") (pin "29") (pinfunction "~{WE}_29") (pintype "input"))
      (node (ref "U3") (pin "29") (pinfunction "~{WE}_29") (pintype "input"))
      (node (ref "U4") (pin "27") (pinfunction "~{WE}_27") (pintype "input"))
    )
  )
)
